# rekick2015-002.net
KiCad netlist of a schematic drawn in EAGLE
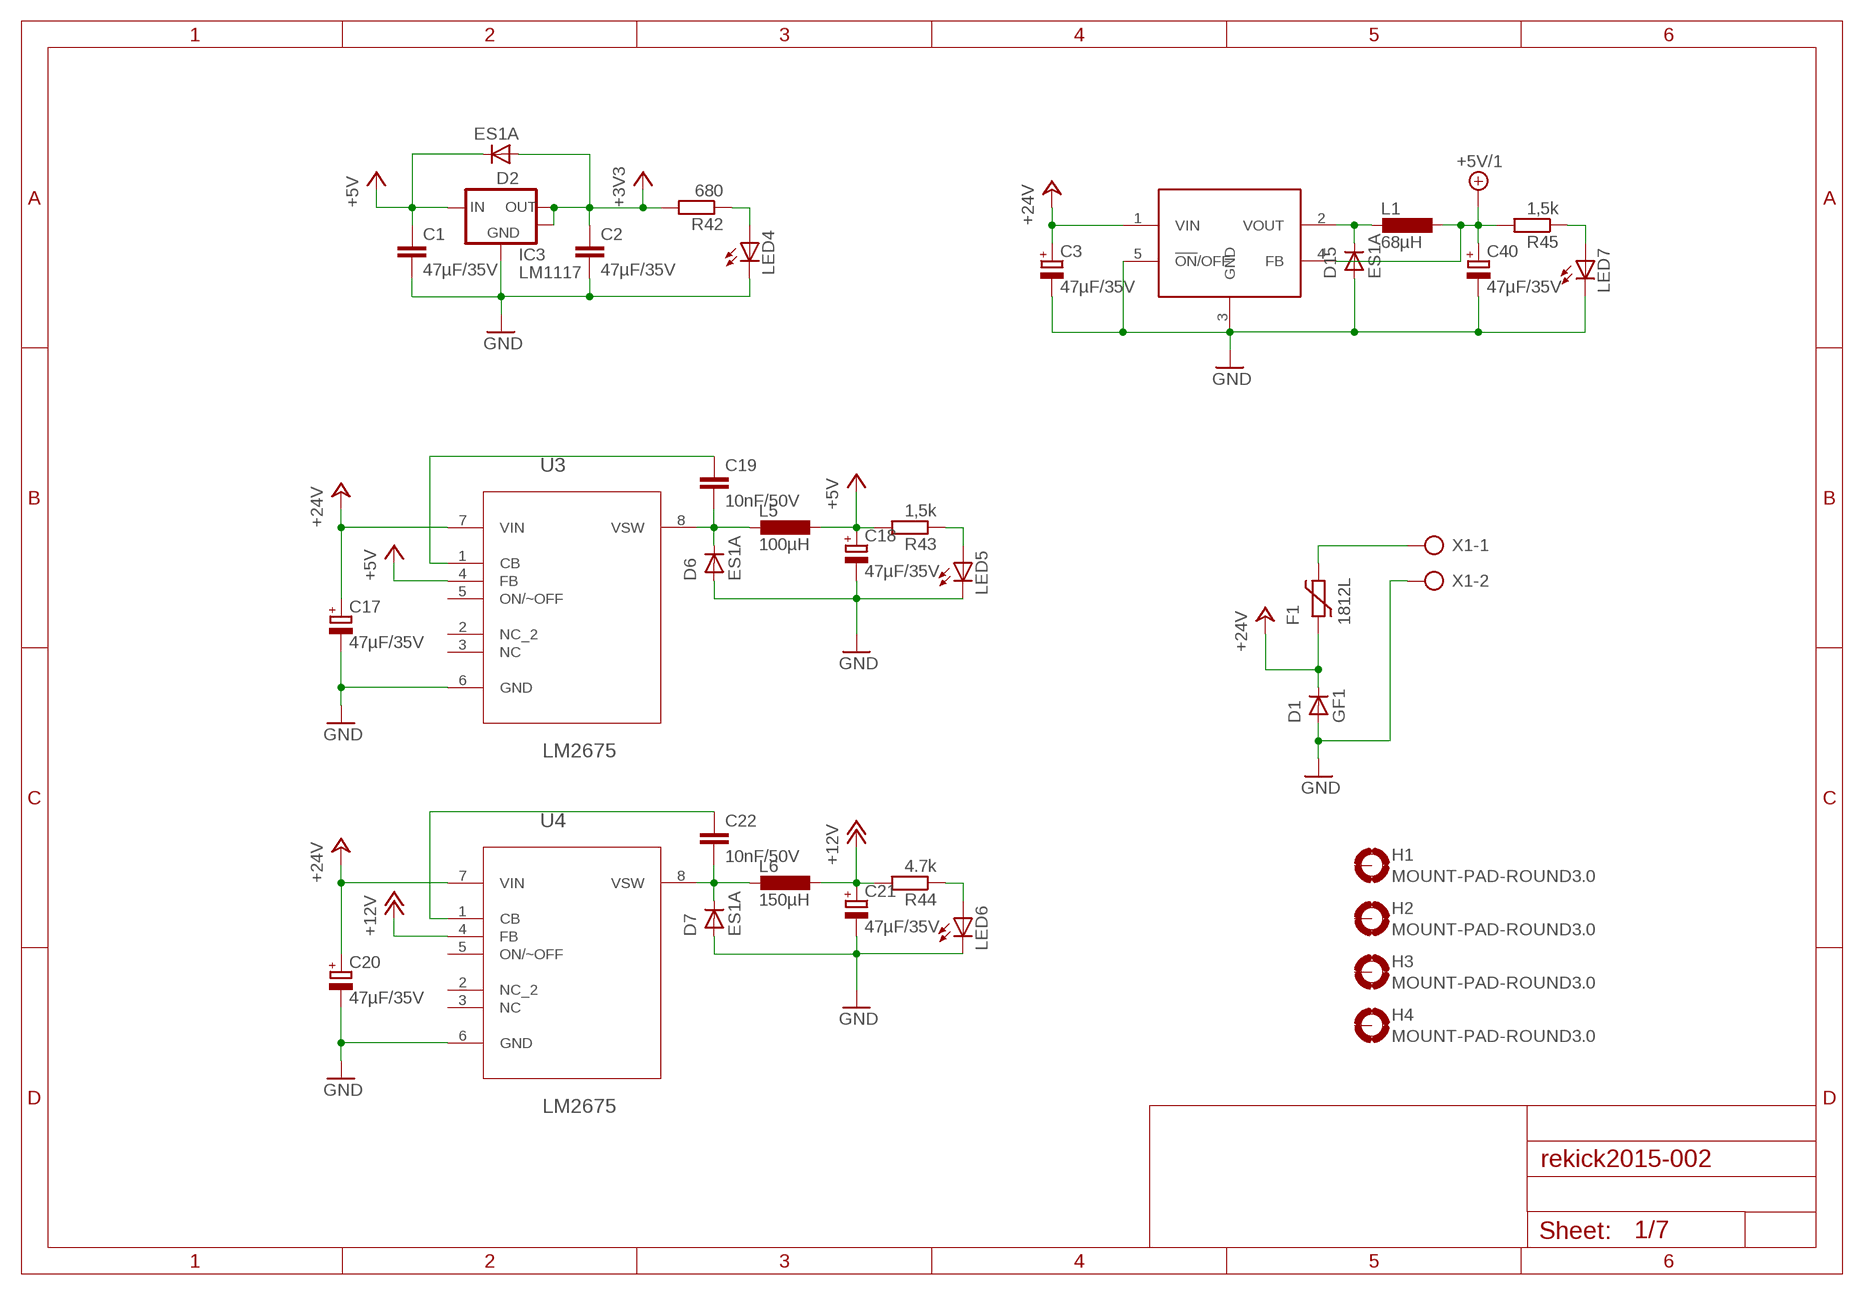
[diagram p0: schematic, sheet 1]
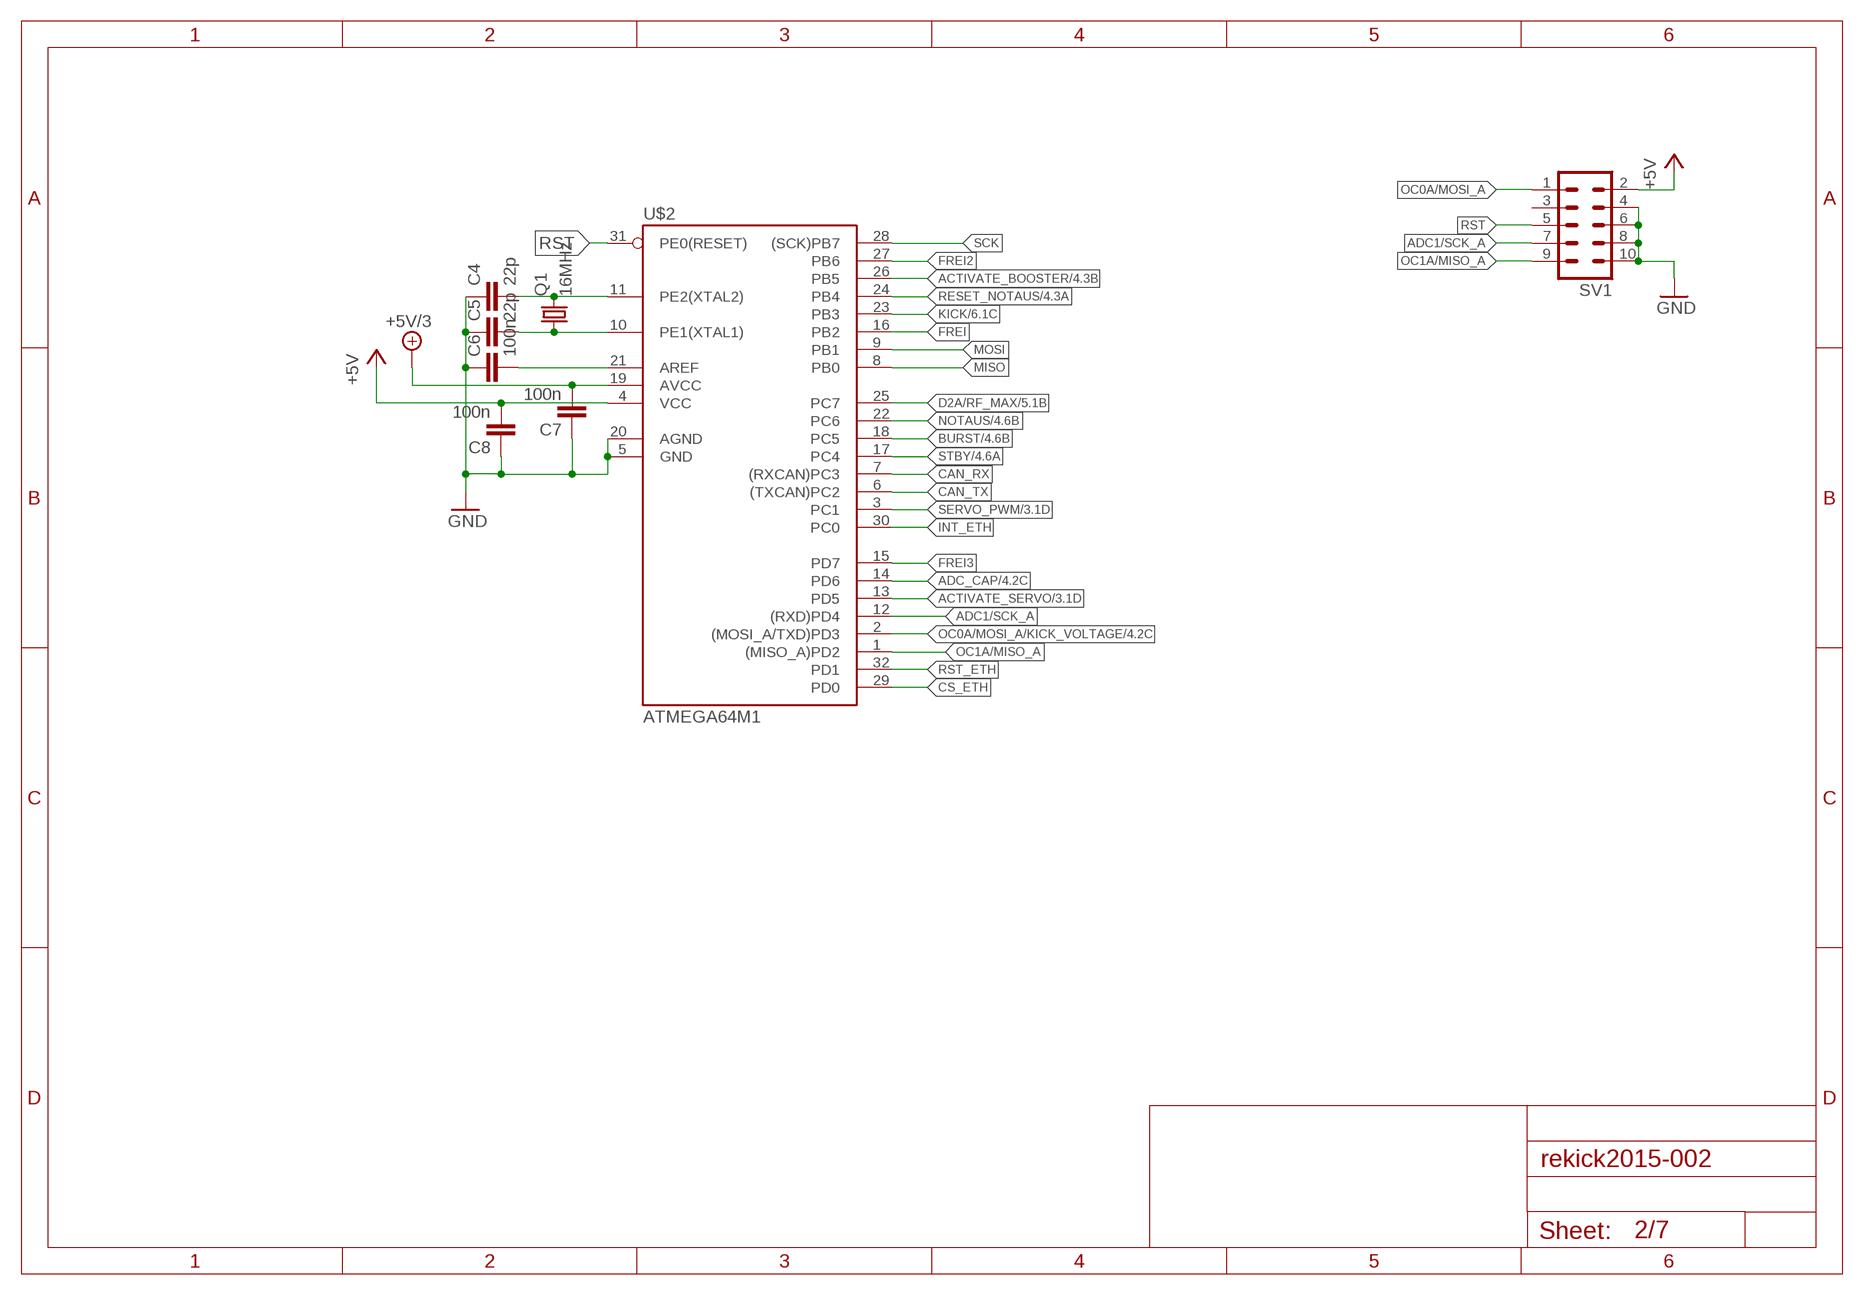
[diagram p1: schematic, sheet 2]
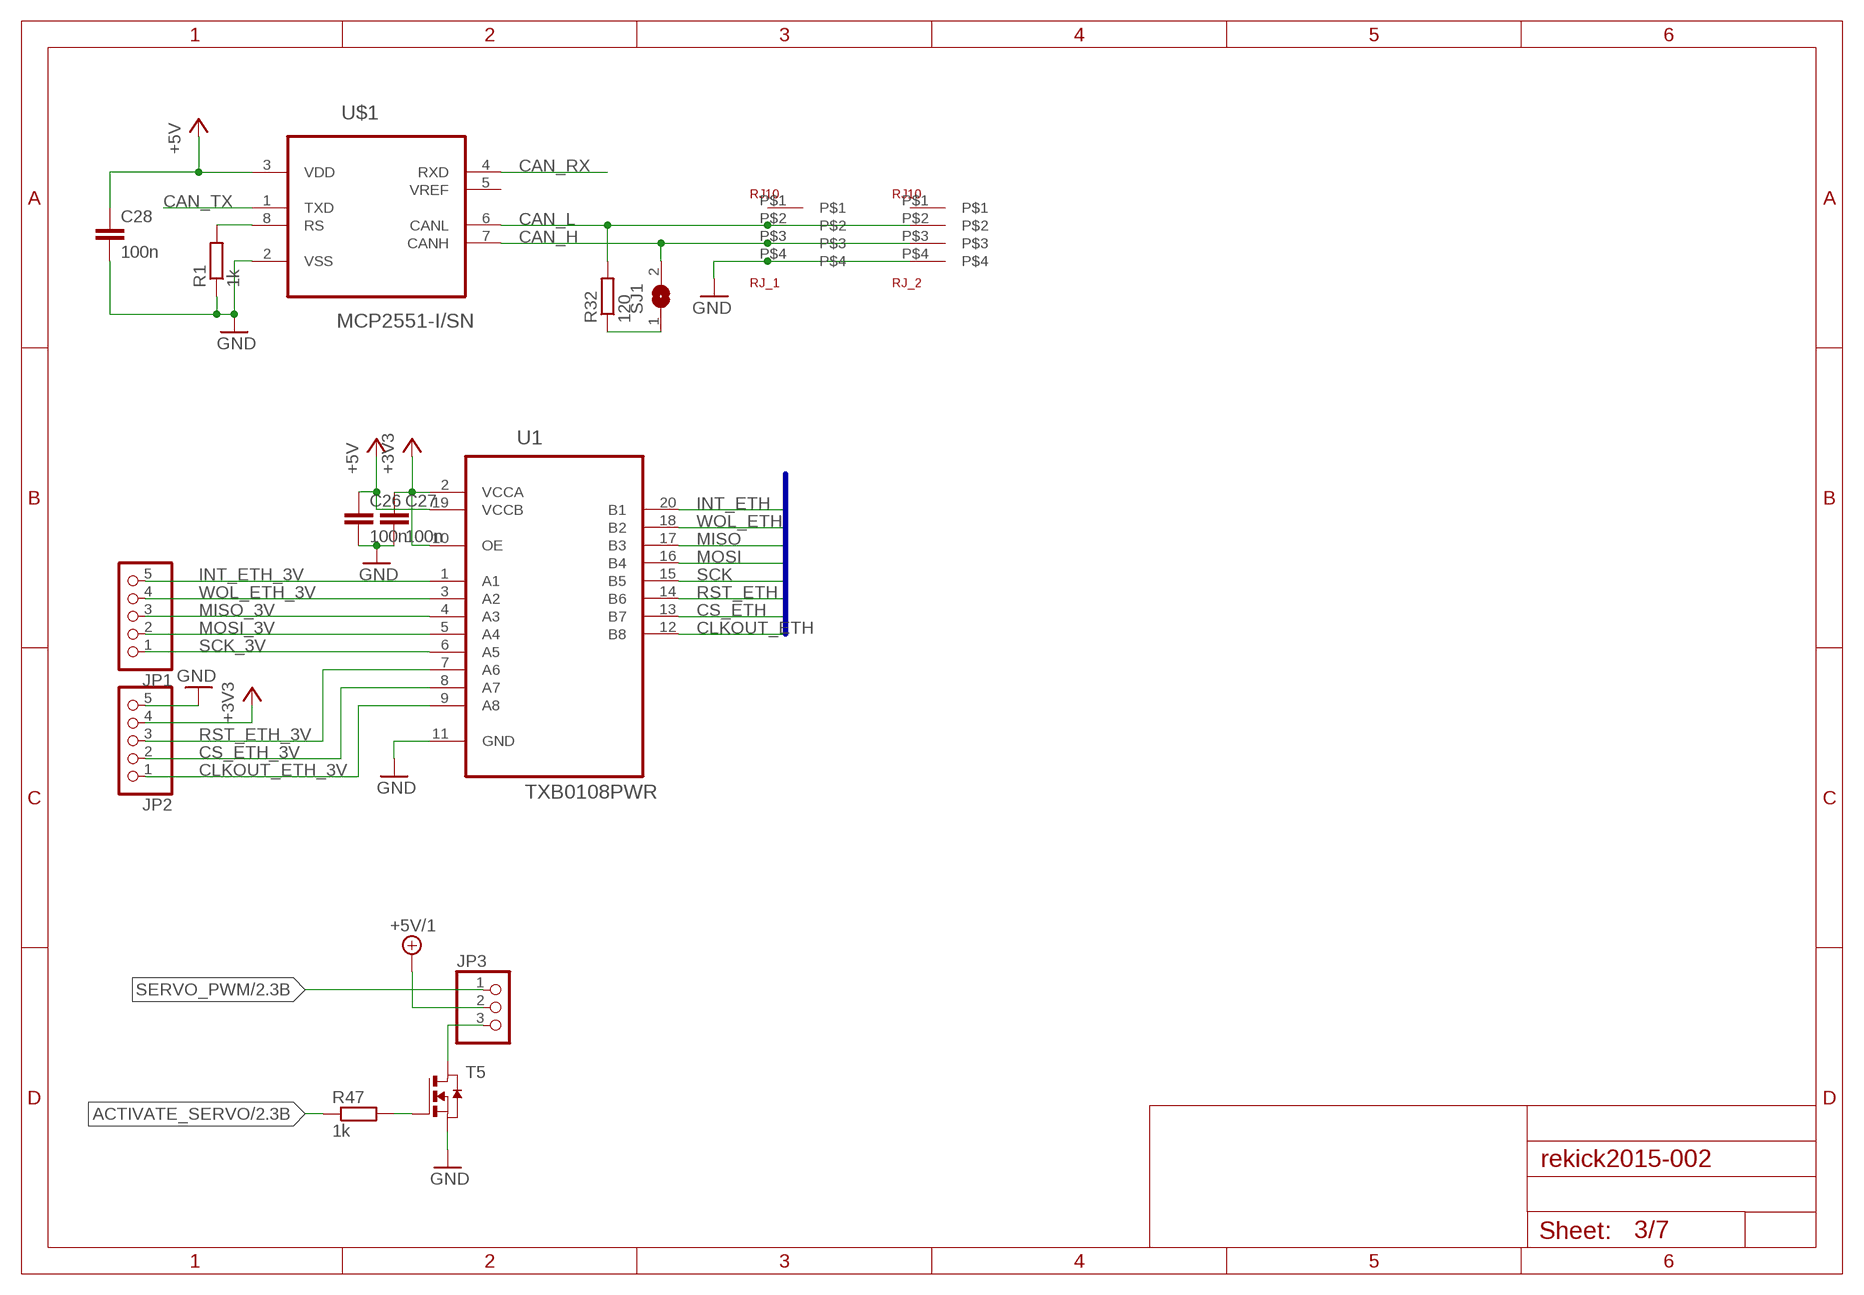
[diagram p2: schematic, sheet 3]
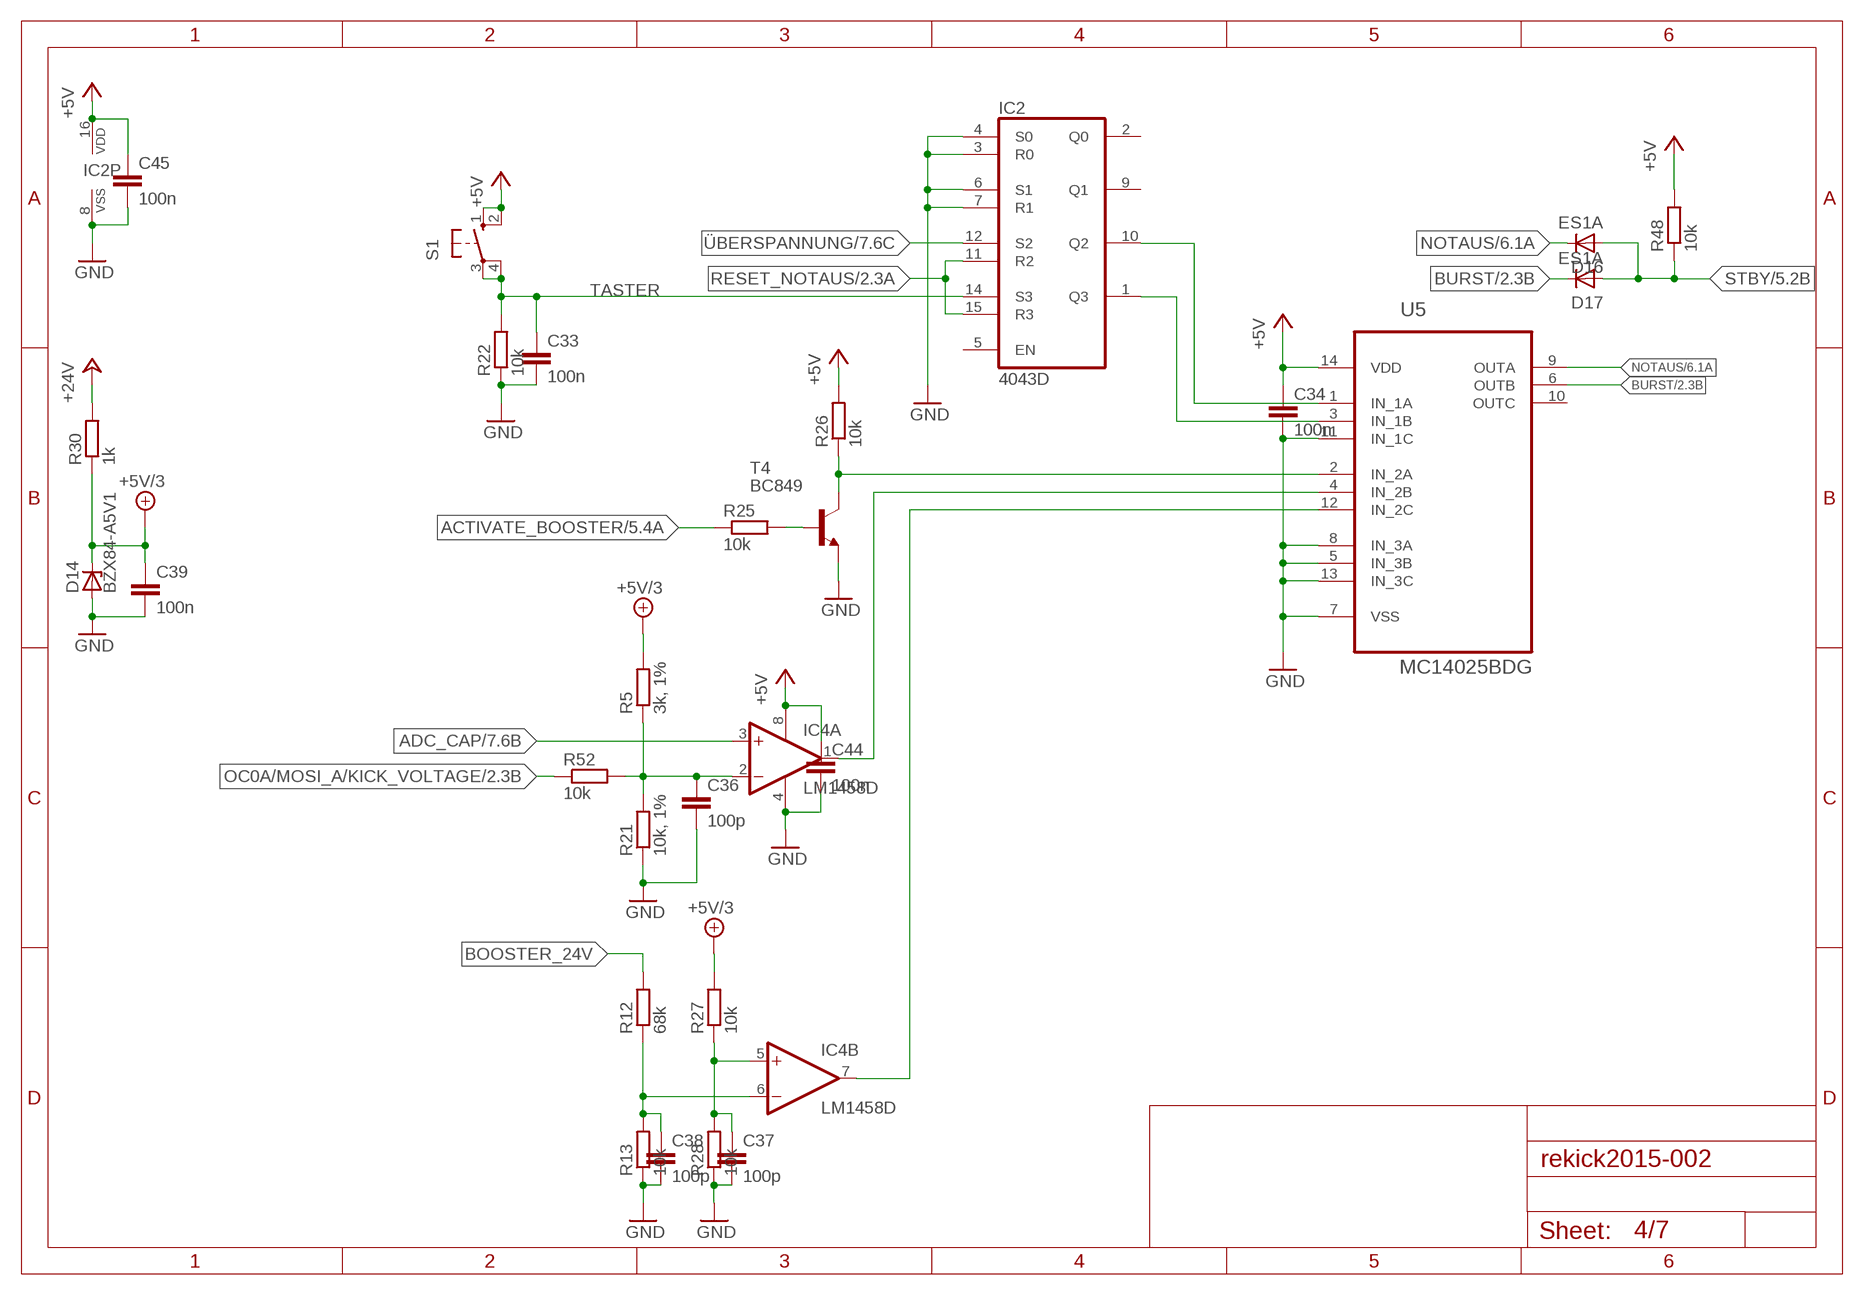
[diagram p3: schematic, sheet 4]
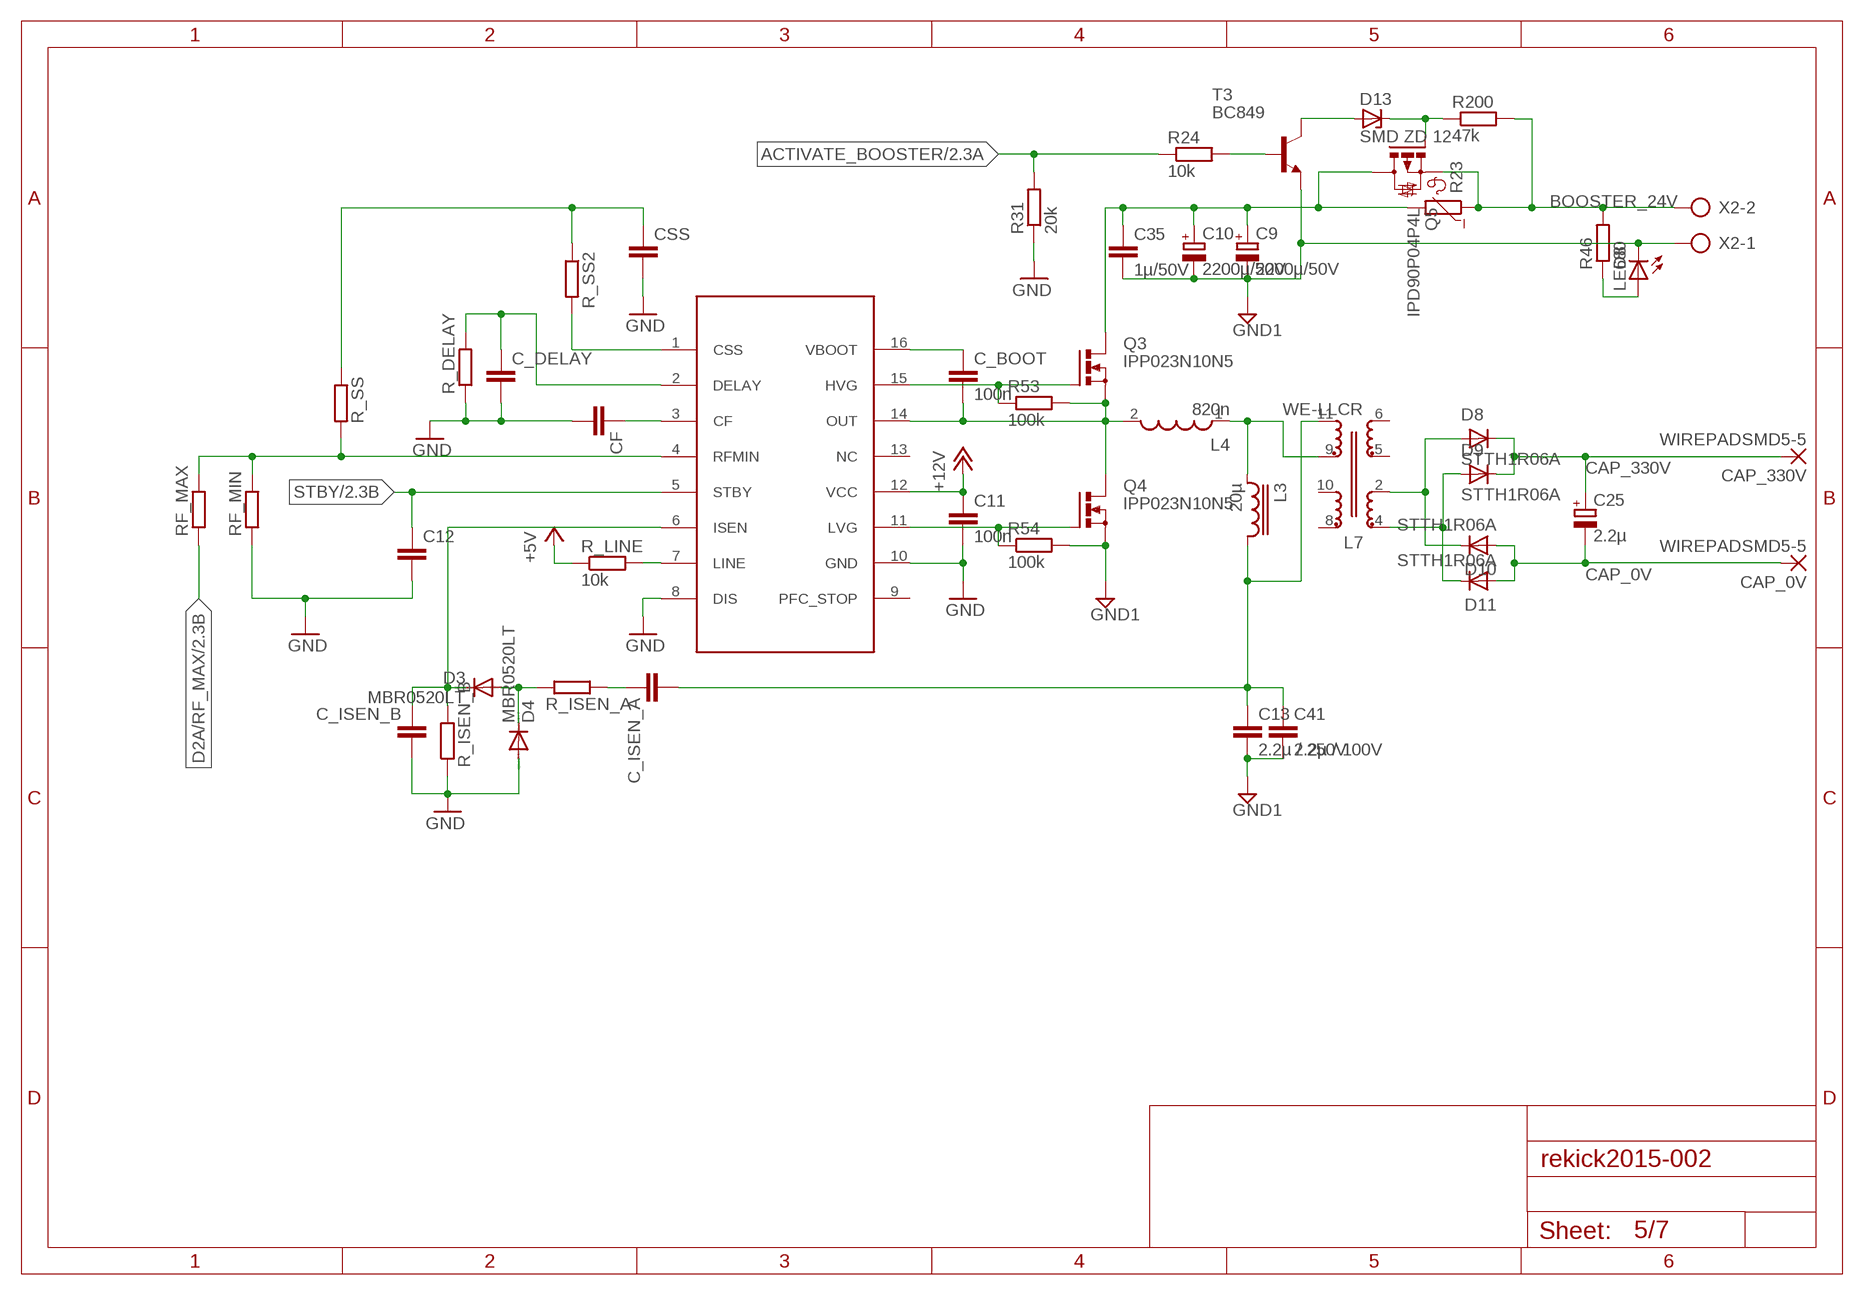
[diagram p4: schematic, sheet 5]
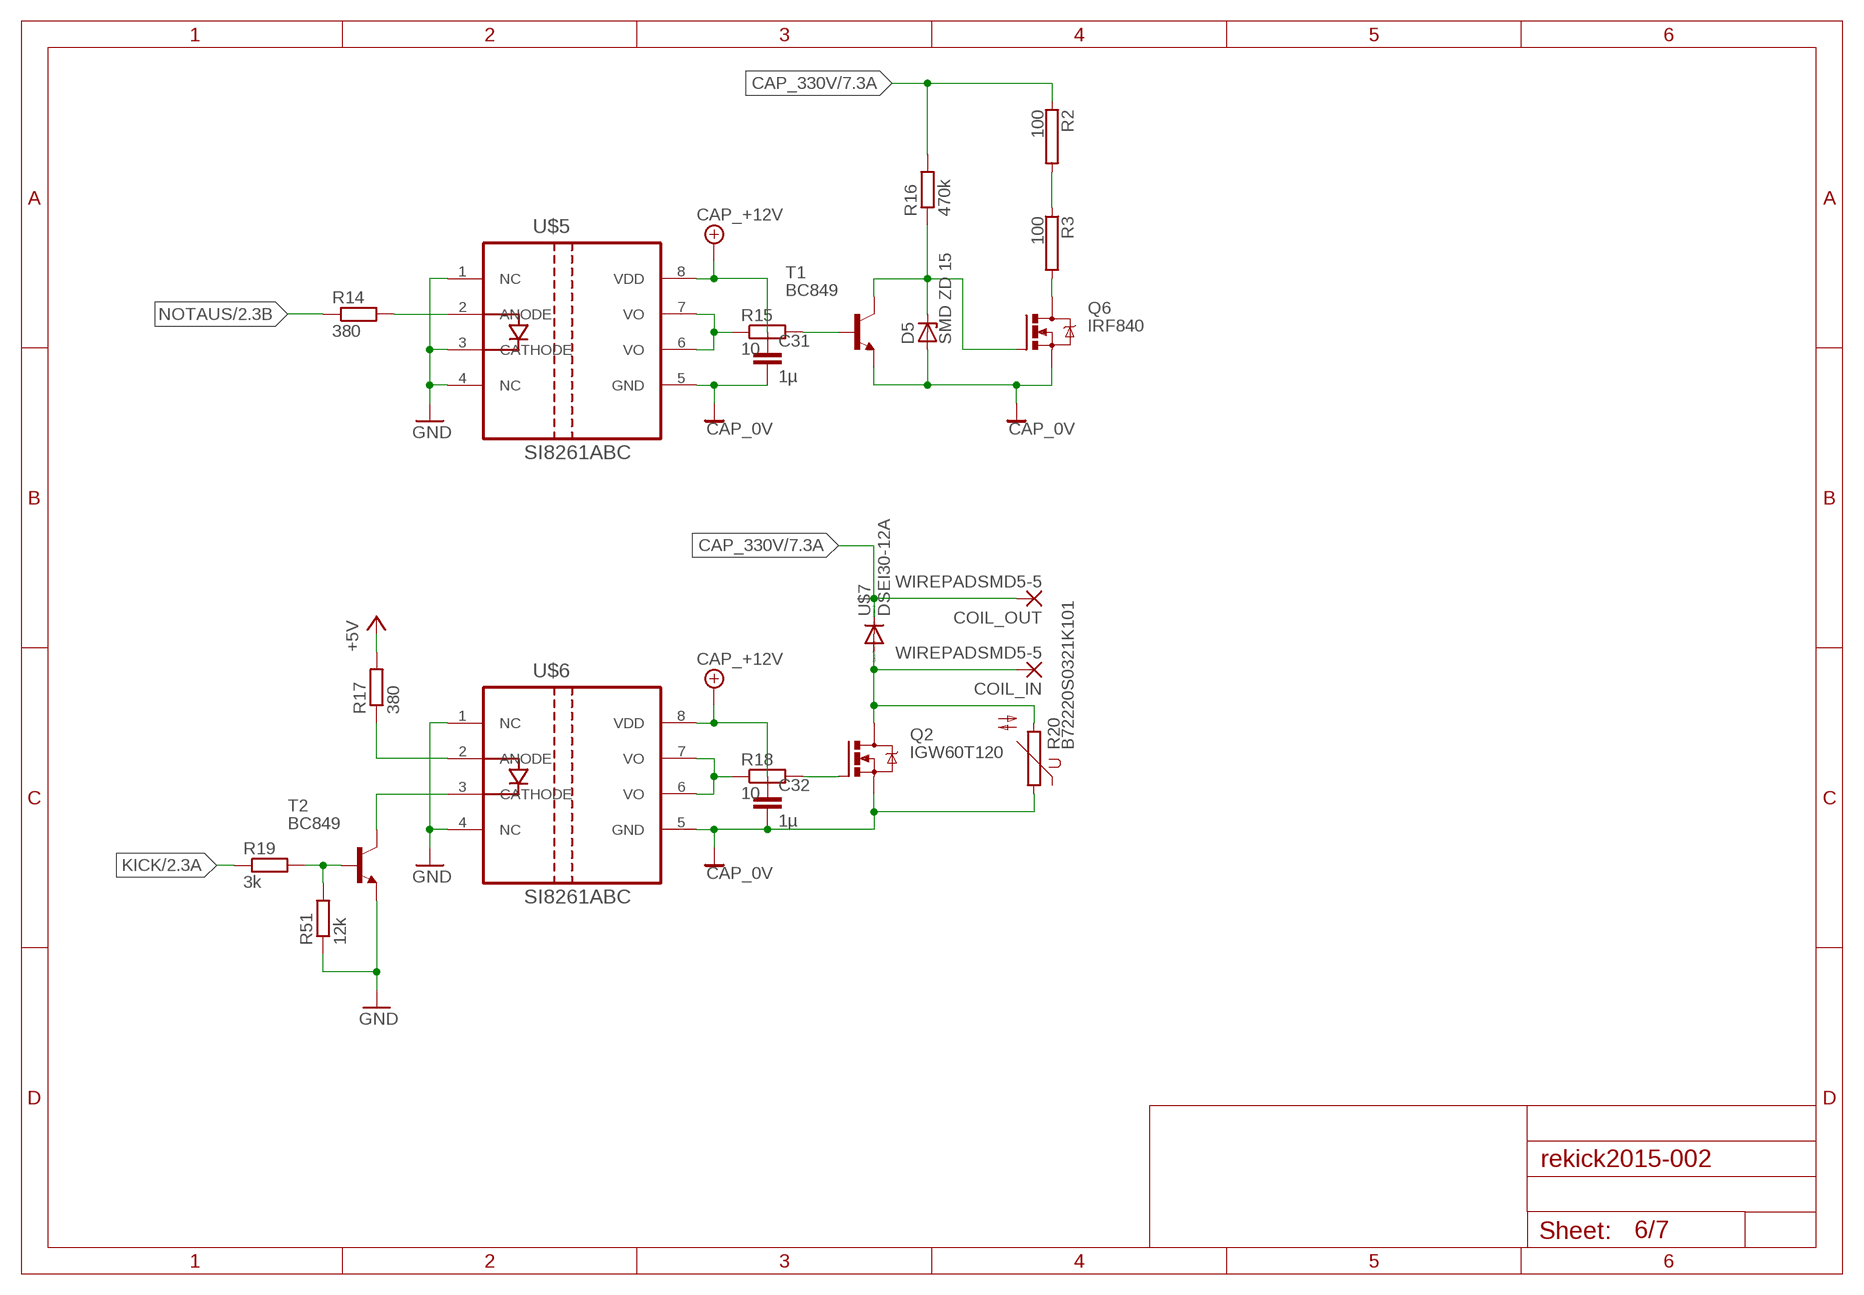
[diagram p5: schematic, sheet 6]
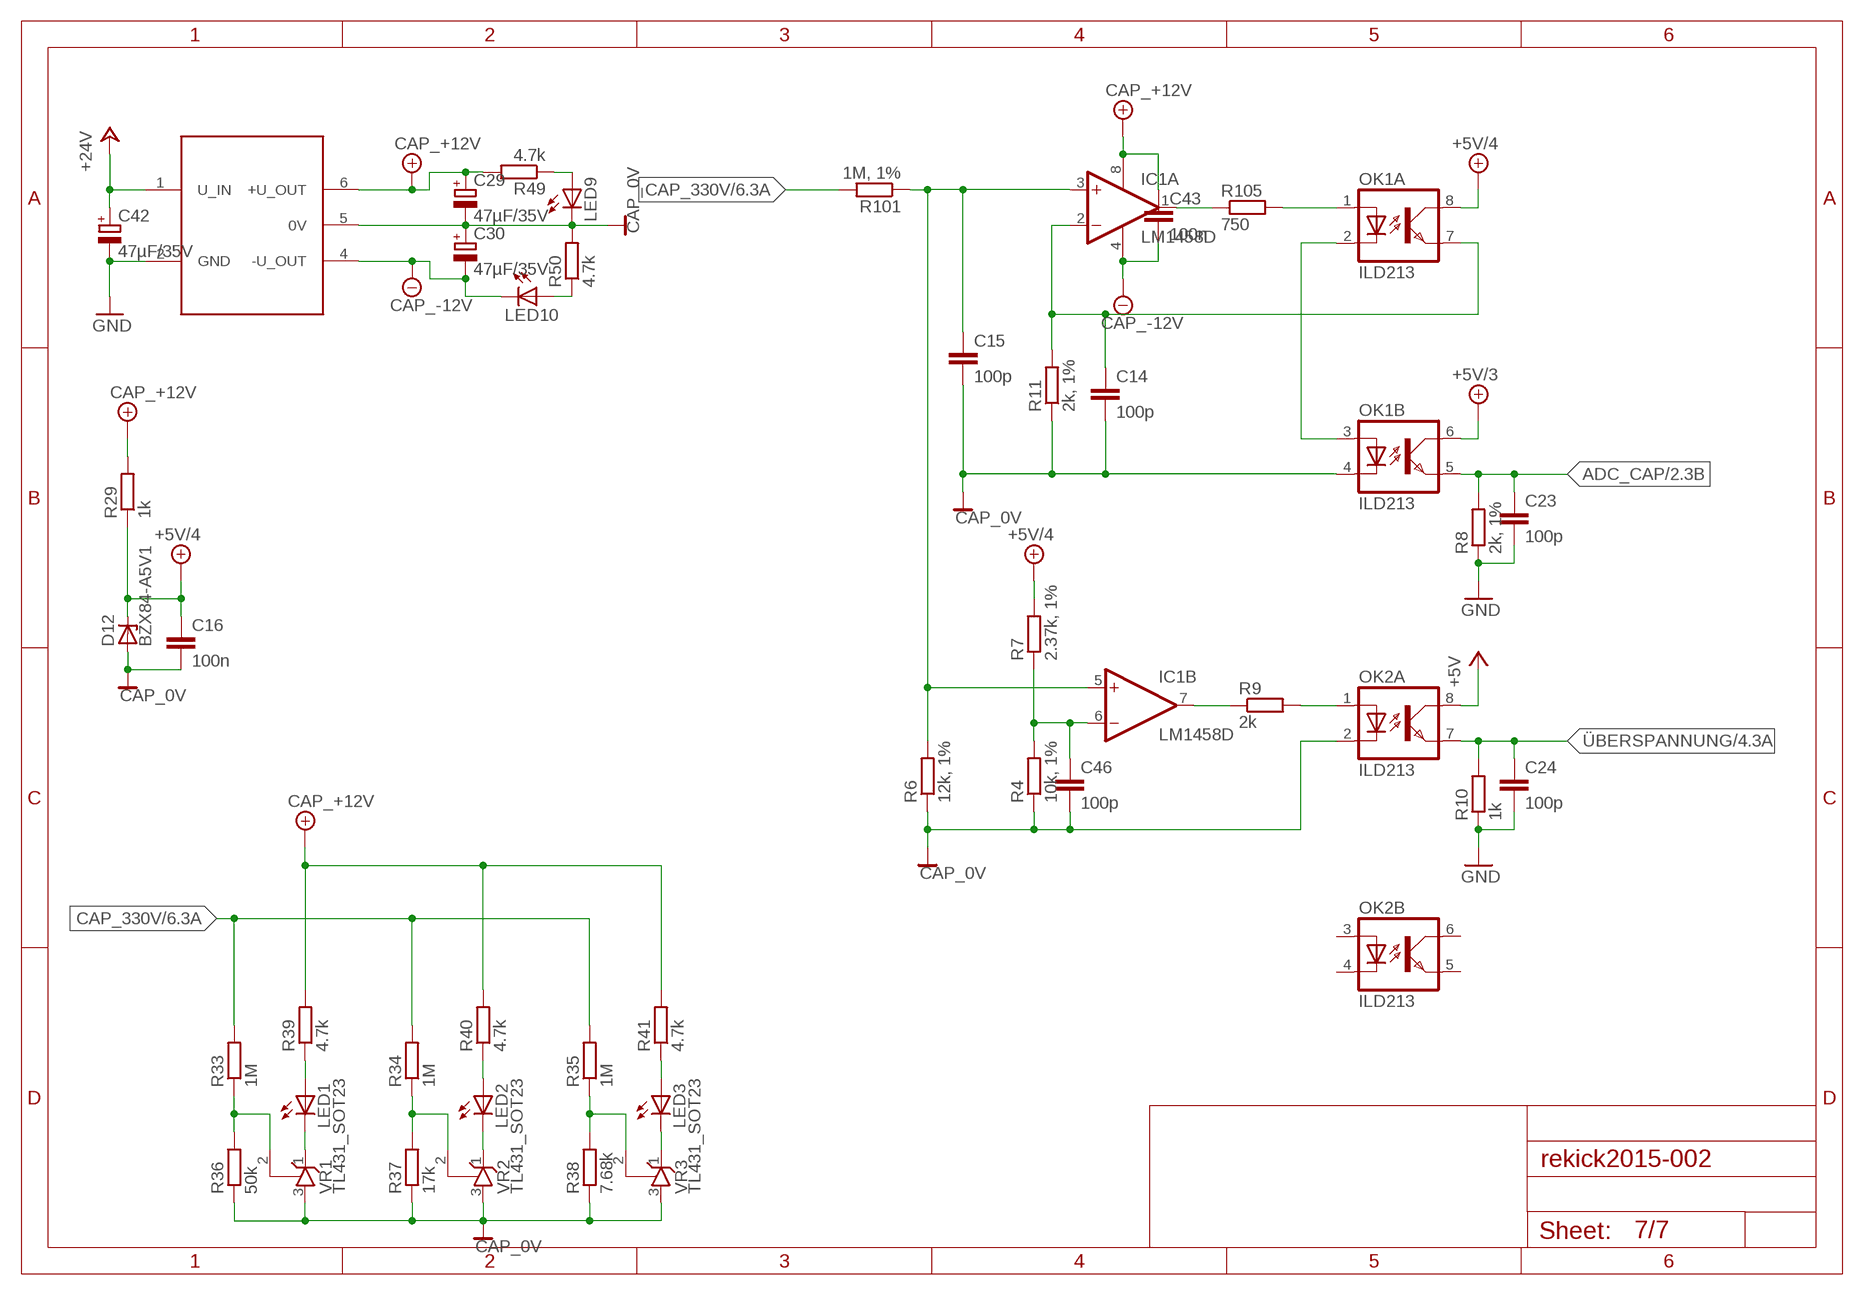
[diagram p6: schematic, sheet 7]

(export (version "E")
  (design (tool "Eeschema 10.0.6"))
  (components
    (comp (ref "C9")
      (value "2200µ/50V")
      (footprint "eagle-import:E5-13")
      (libsource (lib "eagle-import") (part "CPOL-EUE5-13"))
    )
    (comp (ref "C10")
      (value "2200µ/50V")
      (footprint "eagle-import:E5-13")
      (libsource (lib "eagle-import") (part "CPOL-EUE5-13"))
    )
    (comp (ref "C11")
      (value "100n")
      (footprint "eagle-import:C0603")
      (libsource (lib "eagle-import") (part "C-EUC0603"))
    )
    (comp (ref "C12")
      (value "C-EUC0603")
      (footprint "eagle-import:C0603")
      (libsource (lib "eagle-import") (part "C-EUC0603"))
    )
    (comp (ref "C13")
      (value "2.2µ / 250V")
      (footprint "eagle-import:C2220K")
      (libsource (lib "eagle-import") (part "C-EUC2220K"))
    )
    (comp (ref "C25")
      (value "2.2µ")
      (footprint "eagle-import:E5-10,5")
      (libsource (lib "eagle-import") (part "CPOL-EUE5-10.5"))
    )
    (comp (ref "C35")
      (value "1µ/50V")
      (footprint "eagle-import:C0603")
      (libsource (lib "eagle-import") (part "C-EUC0603"))
    )
    (comp (ref "C41")
      (value "2.2µ / 100V")
      (footprint "eagle-import:C1210K")
      (libsource (lib "eagle-import") (part "C-EUC1210K"))
    )
    (comp (ref "CAP_0V")
      (value "WIREPADSMD5-5")
      (footprint "eagle-import:5-5")
      (libsource (lib "eagle-import") (part "WIREPADSMD5-5"))
    )
    (comp (ref "CAP_330V")
      (value "WIREPADSMD5-5")
      (footprint "eagle-import:5-5")
      (libsource (lib "eagle-import") (part "WIREPADSMD5-5"))
    )
    (comp (ref "CF")
      (value "C-EUC0603")
      (footprint "eagle-import:C0603")
      (libsource (lib "eagle-import") (part "C-EUC0603"))
    )
    (comp (ref "CSS")
      (value "C-EUC0603")
      (footprint "eagle-import:C0603")
      (libsource (lib "eagle-import") (part "C-EUC0603"))
    )
    (comp (ref "C_BOOT")
      (value "100n")
      (footprint "eagle-import:C0603")
      (libsource (lib "eagle-import") (part "C-EUC0603"))
    )
    (comp (ref "C_DELAY")
      (value "C-EUC0603")
      (footprint "eagle-import:C0603")
      (libsource (lib "eagle-import") (part "C-EUC0603"))
    )
    (comp (ref "C_ISEN_A")
      (value "C-EUC0603")
      (footprint "eagle-import:C0603")
      (libsource (lib "eagle-import") (part "C-EUC0603"))
    )
    (comp (ref "C_ISEN_B")
      (value "C-EUC0603")
      (footprint "eagle-import:C0603")
      (libsource (lib "eagle-import") (part "C-EUC0603"))
    )
    (comp (ref "D3")
      (value "MBR0520LT")
      (footprint "eagle-import:SOD123")
      (libsource (lib "eagle-import") (part "MBR0520LT"))
    )
    (comp (ref "D4")
      (value "MBR0520LT")
      (footprint "eagle-import:SOD123")
      (libsource (lib "eagle-import") (part "MBR0520LT"))
    )
    (comp (ref "D8")
      (value "STTH1R06A")
      (footprint "eagle-import:SMA-DO214AC")
      (libsource (lib "eagle-import") (part "GF1"))
    )
    (comp (ref "D9")
      (value "STTH1R06A")
      (footprint "eagle-import:SMA-DO214AC")
      (libsource (lib "eagle-import") (part "GF1"))
    )
    (comp (ref "D10")
      (value "STTH1R06A")
      (footprint "eagle-import:SMA-DO214AC")
      (libsource (lib "eagle-import") (part "GF1"))
    )
    (comp (ref "D11")
      (value "STTH1R06A")
      (footprint "eagle-import:SMA-DO214AC")
      (libsource (lib "eagle-import") (part "GF1"))
    )
    (comp (ref "D13")
      (value "SMD ZD 12")
      (footprint "eagle-import:TO236")
      (libsource (lib "eagle-import") (part "BZX84CSMD"))
    )
    (comp (ref "L3")
      (value "20µ")
      (footprint "eagle-import:SRR1210")
      (libsource (lib "eagle-import") (part "SRR1210"))
    )
    (comp (ref "L4")
      (value "820n")
      (footprint "eagle-import:WE-HCI_1890")
      (libsource (lib "eagle-import") (part "WE-HCI_1890"))
    )
    (comp (ref "L7")
      (value "WE-LLCR")
      (footprint "eagle-import:WE-LLCR_ETD34")
      (libsource (lib "eagle-import") (part "WE-LLCR_ETD34"))
    )
    (comp (ref "LED8")
      (value "LEDCHIP-LED0805")
      (footprint "eagle-import:CHIP-LED0805")
      (libsource (lib "eagle-import") (part "LEDCHIP-LED0805"))
    )
    (comp (ref "Q3")
      (value "IPP023N10N5")
      (footprint "eagle-import:TO220BV")
      (libsource (lib "eagle-import") (part "PMOSFET_NTO220BV"))
    )
    (comp (ref "Q4")
      (value "IPP023N10N5")
      (footprint "eagle-import:TO220BV")
      (libsource (lib "eagle-import") (part "PMOSFET_NTO220BV"))
    )
    (comp (ref "Q5")
      (value "IPD90P04P4L")
      (footprint "eagle-import:D-PAK_TO252AA")
      (libsource (lib "eagle-import") (part "IRF?5305R"))
    )
    (comp (ref "R23")
      (value "NTC644A")
      (footprint "eagle-import:N644A")
      (libsource (lib "eagle-import") (part "NTC644A"))
    )
    (comp (ref "R24")
      (value "10k")
      (footprint "eagle-import:R0805")
      (libsource (lib "eagle-import") (part "R-EU_R0805"))
    )
    (comp (ref "R31")
      (value "20k")
      (footprint "eagle-import:R0805")
      (libsource (lib "eagle-import") (part "R-EU_R0805"))
    )
    (comp (ref "R46")
      (value "680")
      (footprint "eagle-import:R0805")
      (libsource (lib "eagle-import") (part "R-EU_R0805"))
    )
    (comp (ref "R53")
      (value "100k")
      (footprint "eagle-import:R0805")
      (libsource (lib "eagle-import") (part "R-EU_R0805"))
    )
    (comp (ref "R54")
      (value "100k")
      (footprint "eagle-import:R0805")
      (libsource (lib "eagle-import") (part "R-EU_R0805"))
    )
    (comp (ref "R200")
      (value "47k")
      (footprint "eagle-import:R0805")
      (libsource (lib "eagle-import") (part "R-EU_R0805"))
    )
    (comp (ref "RF_MAX")
      (value "R-EU_R0805")
      (footprint "eagle-import:R0805")
      (libsource (lib "eagle-import") (part "R-EU_R0805"))
    )
    (comp (ref "RF_MIN")
      (value "R-EU_R0805")
      (footprint "eagle-import:R0805")
      (libsource (lib "eagle-import") (part "R-EU_R0805"))
    )
    (comp (ref "R_DELAY")
      (value "R-EU_R0805")
      (footprint "eagle-import:R0805")
      (libsource (lib "eagle-import") (part "R-EU_R0805"))
    )
    (comp (ref "R_ISEN_A")
      (value "R-EU_R0805")
      (footprint "eagle-import:R0805")
      (libsource (lib "eagle-import") (part "R-EU_R0805"))
    )
    (comp (ref "R_ISEN_B")
      (value "R-EU_R0805")
      (footprint "eagle-import:R0805")
      (libsource (lib "eagle-import") (part "R-EU_R0805"))
    )
    (comp (ref "R_LINE")
      (value "10k")
      (footprint "eagle-import:R0805")
      (libsource (lib "eagle-import") (part "R-EU_R0805"))
    )
    (comp (ref "R_SS")
      (value "R-EU_R0805")
      (footprint "eagle-import:R0805")
      (libsource (lib "eagle-import") (part "R-EU_R0805"))
    )
    (comp (ref "R_SS2")
      (value "R-EU_R0805")
      (footprint "eagle-import:R0805")
      (libsource (lib "eagle-import") (part "R-EU_R0805"))
    )
    (comp (ref "T3")
      (value "BC849")
      (footprint "eagle-import:SOT23")
      (libsource (lib "eagle-import") (part "BC849"))
    )
    (comp (ref "U$3")
      (value "L6599")
      (footprint "eagle-import:SO16")
      (libsource (lib "eagle-import") (part "L6599"))
    )
    (comp (ref "X2")
      (value "AK500/2-H")
      (footprint "eagle-import:AK500_2-H")
      (libsource (lib "eagle-import") (part "AK500/2-H"))
    )
    (comp (ref "C14")
      (value "100p")
      (footprint "eagle-import:C0603")
      (libsource (lib "eagle-import") (part "C-EUC0603"))
    )
    (comp (ref "C15")
      (value "100p")
      (footprint "eagle-import:C0603")
      (libsource (lib "eagle-import") (part "C-EUC0603"))
    )
    (comp (ref "C16")
      (value "100n")
      (footprint "eagle-import:C0603")
      (libsource (lib "eagle-import") (part "C-EUC0603"))
    )
    (comp (ref "C23")
      (value "100p")
      (footprint "eagle-import:C0603")
      (libsource (lib "eagle-import") (part "C-EUC0603"))
    )
    (comp (ref "C24")
      (value "100p")
      (footprint "eagle-import:C0603")
      (libsource (lib "eagle-import") (part "C-EUC0603"))
    )
    (comp (ref "C29")
      (value "47µF/35V")
      (footprint "eagle-import:PANASONIC_D")
      (libsource (lib "eagle-import") (part "CPOL-EUD"))
    )
    (comp (ref "C30")
      (value "47µF/35V")
      (footprint "eagle-import:PANASONIC_D")
      (libsource (lib "eagle-import") (part "CPOL-EUD"))
    )
    (comp (ref "C42")
      (value "47µF/35V")
      (footprint "eagle-import:PANASONIC_D")
      (libsource (lib "eagle-import") (part "CPOL-EUD"))
    )
    (comp (ref "C43")
      (value "100n")
      (footprint "eagle-import:C0603")
      (libsource (lib "eagle-import") (part "C-EUC0603"))
    )
    (comp (ref "C46")
      (value "100p")
      (footprint "eagle-import:C0603")
      (libsource (lib "eagle-import") (part "C-EUC0603"))
    )
    (comp (ref "D12")
      (value "BZX84-A5V1")
      (footprint "eagle-import:TO236")
      (libsource (lib "eagle-import") (part "BZX84CSMD"))
    )
    (comp (ref "IC1")
      (value "LM1458D")
      (footprint "eagle-import:SO08")
      (libsource (lib "eagle-import") (part "1458DLM"))
    )
    (comp (ref "LED1")
      (value "LEDCHIP-LED0805")
      (footprint "eagle-import:CHIP-LED0805")
      (libsource (lib "eagle-import") (part "LEDCHIP-LED0805"))
    )
    (comp (ref "LED2")
      (value "LEDCHIP-LED0805")
      (footprint "eagle-import:CHIP-LED0805")
      (libsource (lib "eagle-import") (part "LEDCHIP-LED0805"))
    )
    (comp (ref "LED3")
      (value "LEDCHIP-LED0805")
      (footprint "eagle-import:CHIP-LED0805")
      (libsource (lib "eagle-import") (part "LEDCHIP-LED0805"))
    )
    (comp (ref "LED9")
      (value "LEDCHIP-LED0805")
      (footprint "eagle-import:CHIP-LED0805")
      (libsource (lib "eagle-import") (part "LEDCHIP-LED0805"))
    )
    (comp (ref "LED10")
      (value "LEDCHIP-LED0805")
      (footprint "eagle-import:CHIP-LED0805")
      (libsource (lib "eagle-import") (part "LEDCHIP-LED0805"))
    )
    (comp (ref "OK1")
      (value "ILD213")
      (footprint "eagle-import:SOIC08")
      (libsource (lib "eagle-import") (part "ILD213"))
    )
    (comp (ref "OK2")
      (value "ILD213")
      (footprint "eagle-import:SOIC08")
      (libsource (lib "eagle-import") (part "ILD213"))
    )
    (comp (ref "R4")
      (value "10k, 1%")
      (footprint "eagle-import:R0805")
      (libsource (lib "eagle-import") (part "R-EU_R0805"))
    )
    (comp (ref "R6")
      (value "12k, 1%")
      (footprint "eagle-import:R0805")
      (libsource (lib "eagle-import") (part "R-EU_R0805"))
    )
    (comp (ref "R7")
      (value "2.37k, 1%")
      (footprint "eagle-import:R0805")
      (libsource (lib "eagle-import") (part "R-EU_R0805"))
    )
    (comp (ref "R8")
      (value "2k, 1%")
      (footprint "eagle-import:R0805")
      (libsource (lib "eagle-import") (part "R-EU_R0805"))
    )
    (comp (ref "R9")
      (value "2k")
      (footprint "eagle-import:R0805")
      (libsource (lib "eagle-import") (part "R-EU_R0805"))
    )
    (comp (ref "R10")
      (value "1k")
      (footprint "eagle-import:R0805")
      (libsource (lib "eagle-import") (part "R-EU_R0805"))
    )
    (comp (ref "R11")
      (value "2k, 1%")
      (footprint "eagle-import:R0805")
      (libsource (lib "eagle-import") (part "R-EU_R0805"))
    )
    (comp (ref "R29")
      (value "1k")
      (footprint "eagle-import:R0805")
      (libsource (lib "eagle-import") (part "R-EU_R0805"))
    )
    (comp (ref "R33")
      (value "1M")
      (footprint "eagle-import:R2512")
      (libsource (lib "eagle-import") (part "R-EU_R2512"))
    )
    (comp (ref "R34")
      (value "1M")
      (footprint "eagle-import:R2512")
      (libsource (lib "eagle-import") (part "R-EU_R2512"))
    )
    (comp (ref "R35")
      (value "1M")
      (footprint "eagle-import:R2512")
      (libsource (lib "eagle-import") (part "R-EU_R2512"))
    )
    (comp (ref "R36")
      (value "50k")
      (footprint "eagle-import:R0805")
      (libsource (lib "eagle-import") (part "R-EU_R0805"))
    )
    (comp (ref "R37")
      (value "17k")
      (footprint "eagle-import:R0805")
      (libsource (lib "eagle-import") (part "R-EU_R0805"))
    )
    (comp (ref "R38")
      (value "7.68k")
      (footprint "eagle-import:R0805")
      (libsource (lib "eagle-import") (part "R-EU_R0805"))
    )
    (comp (ref "R39")
      (value "4.7k")
      (footprint "eagle-import:R0805")
      (libsource (lib "eagle-import") (part "R-EU_R0805"))
    )
    (comp (ref "R40")
      (value "4.7k")
      (footprint "eagle-import:R0805")
      (libsource (lib "eagle-import") (part "R-EU_R0805"))
    )
    (comp (ref "R41")
      (value "4.7k")
      (footprint "eagle-import:R0805")
      (libsource (lib "eagle-import") (part "R-EU_R0805"))
    )
    (comp (ref "R49")
      (value "4.7k")
      (footprint "eagle-import:R0805")
      (libsource (lib "eagle-import") (part "R-EU_R0805"))
    )
    (comp (ref "R50")
      (value "4.7k")
      (footprint "eagle-import:R0805")
      (libsource (lib "eagle-import") (part "R-EU_R0805"))
    )
    (comp (ref "R101")
      (value "1M, 1%")
      (footprint "eagle-import:R2512")
      (libsource (lib "eagle-import") (part "R-EU_R2512"))
    )
    (comp (ref "R105")
      (value "750")
      (footprint "eagle-import:R0805")
      (libsource (lib "eagle-import") (part "R-EU_R0805"))
    )
    (comp (ref "U$4")
      (value "TMH-D")
      (footprint "eagle-import:TMH-D")
      (libsource (lib "eagle-import") (part "TMH-D"))
    )
    (comp (ref "VR1")
      (value "TL431_SOT23")
      (footprint "eagle-import:SOT23")
      (libsource (lib "eagle-import") (part "TL431_SOT23"))
    )
    (comp (ref "VR2")
      (value "TL431_SOT23")
      (footprint "eagle-import:SOT23")
      (libsource (lib "eagle-import") (part "TL431_SOT23"))
    )
    (comp (ref "VR3")
      (value "TL431_SOT23")
      (footprint "eagle-import:SOT23")
      (libsource (lib "eagle-import") (part "TL431_SOT23"))
    )
    (comp (ref "C4")
      (value "22p")
      (footprint "eagle-import:C0603")
      (libsource (lib "eagle-import") (part "C-EUC0603"))
    )
    (comp (ref "C5")
      (value "22p")
      (footprint "eagle-import:C0603")
      (libsource (lib "eagle-import") (part "C-EUC0603"))
    )
    (comp (ref "C6")
      (value "100n")
      (footprint "eagle-import:C0603")
      (libsource (lib "eagle-import") (part "C-EUC0603"))
    )
    (comp (ref "C7")
      (value "100n")
      (footprint "eagle-import:C0603")
      (libsource (lib "eagle-import") (part "C-EUC0603"))
    )
    (comp (ref "C8")
      (value "100n")
      (footprint "eagle-import:C0603")
      (libsource (lib "eagle-import") (part "C-EUC0603"))
    )
    (comp (ref "Q1")
      (value "16MHz")
      (footprint "eagle-import:HC49UP")
      (libsource (lib "eagle-import") (part "CRYSTALHC49UP"))
    )
    (comp (ref "SV1")
      (value "ML10")
      (footprint "eagle-import:ML10")
      (libsource (lib "eagle-import") (part "ML10"))
    )
    (comp (ref "U$2")
      (value "ATMEGA64M1")
      (footprint "eagle-import:TQFP32-08")
      (libsource (lib "eagle-import") (part "ATMEGA64M1"))
    )
    (comp (ref "C33")
      (value "100n")
      (footprint "eagle-import:C0603")
      (libsource (lib "eagle-import") (part "C-EUC0603"))
    )
    (comp (ref "C34")
      (value "100n")
      (footprint "eagle-import:C0603")
      (libsource (lib "eagle-import") (part "C-EUC0603"))
    )
    (comp (ref "C36")
      (value "100p")
      (footprint "eagle-import:C0603")
      (libsource (lib "eagle-import") (part "C-EUC0603"))
    )
    (comp (ref "C37")
      (value "100p")
      (footprint "eagle-import:C0603")
      (libsource (lib "eagle-import") (part "C-EUC0603"))
    )
    (comp (ref "C38")
      (value "100p")
      (footprint "eagle-import:C0603")
      (libsource (lib "eagle-import") (part "C-EUC0603"))
    )
    (comp (ref "C39")
      (value "100n")
      (footprint "eagle-import:C0603")
      (libsource (lib "eagle-import") (part "C-EUC0603"))
    )
    (comp (ref "C44")
      (value "100n")
      (footprint "eagle-import:C0603")
      (libsource (lib "eagle-import") (part "C-EUC0603"))
    )
    (comp (ref "C45")
      (value "100n")
      (footprint "eagle-import:C0603")
      (libsource (lib "eagle-import") (part "C-EUC0603"))
    )
    (comp (ref "D14")
      (value "BZX84-A5V1")
      (footprint "eagle-import:TO236")
      (libsource (lib "eagle-import") (part "BZX84CSMD"))
    )
    (comp (ref "D16")
      (value "ES1A")
      (footprint "eagle-import:SMA-DO214AC")
      (libsource (lib "eagle-import") (part "GF1"))
    )
    (comp (ref "D17")
      (value "ES1A")
      (footprint "eagle-import:SMA-DO214AC")
      (libsource (lib "eagle-import") (part "GF1"))
    )
    (comp (ref "IC2")
      (value "4043D")
      (footprint "eagle-import:SO16")
      (libsource (lib "eagle-import") (part "4043D"))
    )
    (comp (ref "IC4")
      (value "LM1458D")
      (footprint "eagle-import:SO08")
      (libsource (lib "eagle-import") (part "1458DLM"))
    )
    (comp (ref "R5")
      (value "3k, 1%")
      (footprint "eagle-import:R0805")
      (libsource (lib "eagle-import") (part "R-EU_R0805"))
    )
    (comp (ref "R12")
      (value "68k")
      (footprint "eagle-import:R0805")
      (libsource (lib "eagle-import") (part "R-EU_R0805"))
    )
    (comp (ref "R13")
      (value "10k")
      (footprint "eagle-import:R0805")
      (libsource (lib "eagle-import") (part "R-EU_R0805"))
    )
    (comp (ref "R21")
      (value "10k, 1%")
      (footprint "eagle-import:R0805")
      (libsource (lib "eagle-import") (part "R-EU_R0805"))
    )
    (comp (ref "R22")
      (value "10k")
      (footprint "eagle-import:R0805")
      (libsource (lib "eagle-import") (part "R-EU_R0805"))
    )
    (comp (ref "R25")
      (value "10k")
      (footprint "eagle-import:R0805")
      (libsource (lib "eagle-import") (part "R-EU_R0805"))
    )
    (comp (ref "R26")
      (value "10k")
      (footprint "eagle-import:R0805")
      (libsource (lib "eagle-import") (part "R-EU_R0805"))
    )
    (comp (ref "R27")
      (value "10k")
      (footprint "eagle-import:R0805")
      (libsource (lib "eagle-import") (part "R-EU_R0805"))
    )
    (comp (ref "R28")
      (value "10k")
      (footprint "eagle-import:R0805")
      (libsource (lib "eagle-import") (part "R-EU_R0805"))
    )
    (comp (ref "R30")
      (value "1k")
      (footprint "eagle-import:R0805")
      (libsource (lib "eagle-import") (part "R-EU_R0805"))
    )
    (comp (ref "R48")
      (value "10k")
      (footprint "eagle-import:R0805")
      (libsource (lib "eagle-import") (part "R-EU_R0805"))
    )
    (comp (ref "R52")
      (value "10k")
      (footprint "eagle-import:R0805")
      (libsource (lib "eagle-import") (part "R-EU_R0805"))
    )
    (comp (ref "S1")
      (value "10-XX")
      (footprint "eagle-import:B3F-10XX")
      (libsource (lib "eagle-import") (part "10-XX"))
    )
    (comp (ref "T4")
      (value "BC849")
      (footprint "eagle-import:SOT23")
      (libsource (lib "eagle-import") (part "BC849"))
    )
    (comp (ref "U5")
      (value "MC14025BDG")
      (footprint "eagle-import:SOIC127P600X175-14N")
      (libsource (lib "eagle-import") (part "MC14025BDG"))
    )
    (comp (ref "C1")
      (value "47µF/35V")
      (footprint "eagle-import:C0603")
      (libsource (lib "eagle-import") (part "C-EUC0603"))
    )
    (comp (ref "C2")
      (value "47µF/35V")
      (footprint "eagle-import:C0603")
      (libsource (lib "eagle-import") (part "C-EUC0603"))
    )
    (comp (ref "C3")
      (value "47µF/35V")
      (footprint "eagle-import:PANASONIC_D")
      (libsource (lib "eagle-import") (part "CPOL-EUD"))
    )
    (comp (ref "C17")
      (value "47µF/35V")
      (footprint "eagle-import:PANASONIC_D")
      (libsource (lib "eagle-import") (part "CPOL-EUD"))
    )
    (comp (ref "C18")
      (value "47µF/35V")
      (footprint "eagle-import:PANASONIC_D")
      (libsource (lib "eagle-import") (part "CPOL-EUD"))
    )
    (comp (ref "C19")
      (value "10nF/50V")
      (footprint "eagle-import:C0603")
      (libsource (lib "eagle-import") (part "C-EUC0603"))
    )
    (comp (ref "C20")
      (value "47µF/35V")
      (footprint "eagle-import:PANASONIC_D")
      (libsource (lib "eagle-import") (part "CPOL-EUD"))
    )
    (comp (ref "C21")
      (value "47µF/35V")
      (footprint "eagle-import:PANASONIC_D")
      (libsource (lib "eagle-import") (part "CPOL-EUD"))
    )
    (comp (ref "C22")
      (value "10nF/50V")
      (footprint "eagle-import:C0603")
      (libsource (lib "eagle-import") (part "C-EUC0603"))
    )
    (comp (ref "C40")
      (value "47µF/35V")
      (footprint "eagle-import:PANASONIC_D")
      (libsource (lib "eagle-import") (part "CPOL-EUD"))
    )
    (comp (ref "D1")
      (value "GF1")
      (footprint "eagle-import:SMA-DO214AC")
      (libsource (lib "eagle-import") (part "GF1"))
    )
    (comp (ref "D2")
      (value "ES1A")
      (footprint "eagle-import:SMA-DO214AC")
      (libsource (lib "eagle-import") (part "GF1"))
    )
    (comp (ref "D6")
      (value "ES1A")
      (footprint "eagle-import:SMA-DO214AC")
      (libsource (lib "eagle-import") (part "GF1"))
    )
    (comp (ref "D7")
      (value "ES1A")
      (footprint "eagle-import:SMA-DO214AC")
      (libsource (lib "eagle-import") (part "GF1"))
    )
    (comp (ref "D15")
      (value "ES1A")
      (footprint "eagle-import:SMA-DO214AC")
      (libsource (lib "eagle-import") (part "GF1"))
    )
    (comp (ref "F1")
      (value "1812L")
      (footprint "eagle-import:1812L")
      (libsource (lib "eagle-import") (part "1812L"))
    )
    (comp (ref "H1")
      (value "MOUNT-PAD-ROUND3.0")
      (footprint "eagle-import:3,0-PAD")
      (libsource (lib "eagle-import") (part "MOUNT-PAD-ROUND3.0"))
    )
    (comp (ref "H2")
      (value "MOUNT-PAD-ROUND3.0")
      (footprint "eagle-import:3,0-PAD")
      (libsource (lib "eagle-import") (part "MOUNT-PAD-ROUND3.0"))
    )
    (comp (ref "H3")
      (value "MOUNT-PAD-ROUND3.0")
      (footprint "eagle-import:3,0-PAD")
      (libsource (lib "eagle-import") (part "MOUNT-PAD-ROUND3.0"))
    )
    (comp (ref "H4")
      (value "MOUNT-PAD-ROUND3.0")
      (footprint "eagle-import:3,0-PAD")
      (libsource (lib "eagle-import") (part "MOUNT-PAD-ROUND3.0"))
    )
    (comp (ref "IC3")
      (value "LM1117")
      (footprint "eagle-import:SOT223")
      (libsource (lib "eagle-import") (part "LM1117"))
    )
    (comp (ref "L1")
      (value "68µH")
      (footprint "eagle-import:PISM")
      (libsource (lib "eagle-import") (part "L-EUPISM"))
    )
    (comp (ref "L5")
      (value "100µH")
      (footprint "eagle-import:PISM")
      (libsource (lib "eagle-import") (part "L-EUPISM"))
    )
    (comp (ref "L6")
      (value "150µH")
      (footprint "eagle-import:PISM")
      (libsource (lib "eagle-import") (part "L-EUPISM"))
    )
    (comp (ref "LED4")
      (value "LEDCHIP-LED0805")
      (footprint "eagle-import:CHIP-LED0805")
      (libsource (lib "eagle-import") (part "LEDCHIP-LED0805"))
    )
    (comp (ref "LED5")
      (value "LEDCHIP-LED0805")
      (footprint "eagle-import:CHIP-LED0805")
      (libsource (lib "eagle-import") (part "LEDCHIP-LED0805"))
    )
    (comp (ref "LED6")
      (value "LEDCHIP-LED0805")
      (footprint "eagle-import:CHIP-LED0805")
      (libsource (lib "eagle-import") (part "LEDCHIP-LED0805"))
    )
    (comp (ref "LED7")
      (value "LEDCHIP-LED0805")
      (footprint "eagle-import:CHIP-LED0805")
      (libsource (lib "eagle-import") (part "LEDCHIP-LED0805"))
    )
    (comp (ref "R42")
      (value "680")
      (footprint "eagle-import:R0805")
      (libsource (lib "eagle-import") (part "R-EU_R0805"))
    )
    (comp (ref "R43")
      (value "1,5k")
      (footprint "eagle-import:R0805")
      (libsource (lib "eagle-import") (part "R-EU_R0805"))
    )
    (comp (ref "R44")
      (value "4.7k")
      (footprint "eagle-import:R0805")
      (libsource (lib "eagle-import") (part "R-EU_R0805"))
    )
    (comp (ref "R45")
      (value "1,5k")
      (footprint "eagle-import:R0805")
      (libsource (lib "eagle-import") (part "R-EU_R0805"))
    )
    (comp (ref "U$8")
      (value "LM2576")
      (footprint "eagle-import:TO220511")
      (libsource (lib "eagle-import") (part "LM2576"))
    )
    (comp (ref "U3")
      (value "LM2675")
      (footprint "eagle-import:SOIC127P620X175-8N")
      (fields (field (name "MPN") "LM2675M-3.3"))
      (libsource (lib "eagle-import") (part "LM2675M-3.3"))
    )
    (comp (ref "U4")
      (value "LM2675")
      (footprint "eagle-import:SOIC127P620X175-8N")
      (fields (field (name "MPN") "LM2675M-3.3"))
      (libsource (lib "eagle-import") (part "LM2675M-3.3"))
    )
    (comp (ref "X1")
      (value "AK500/2-H")
      (footprint "eagle-import:AK500_2-H")
      (libsource (lib "eagle-import") (part "AK500/2-H"))
    )
    (comp (ref "C31")
      (value "1µ")
      (footprint "eagle-import:C0603")
      (libsource (lib "eagle-import") (part "C-EUC0603"))
    )
    (comp (ref "C32")
      (value "1µ")
      (footprint "eagle-import:C0603")
      (libsource (lib "eagle-import") (part "C-EUC0603"))
    )
    (comp (ref "COIL_IN")
      (value "WIREPADSMD5-5")
      (footprint "eagle-import:5-5")
      (libsource (lib "eagle-import") (part "WIREPADSMD5-5"))
    )
    (comp (ref "COIL_OUT")
      (value "WIREPADSMD5-5")
      (footprint "eagle-import:5-5")
      (libsource (lib "eagle-import") (part "WIREPADSMD5-5"))
    )
    (comp (ref "D5")
      (value "SMD ZD 15")
      (footprint "eagle-import:TO236")
      (libsource (lib "eagle-import") (part "BZX84CSMD"))
    )
    (comp (ref "Q2")
      (value "IGW60T120")
      (footprint "eagle-import:TO247BV")
      (libsource (lib "eagle-import") (part "IRFPC40"))
    )
    (comp (ref "Q6")
      (value "IRF840")
      (footprint "eagle-import:TO220BV")
      (libsource (lib "eagle-import") (part "IRF740"))
    )
    (comp (ref "R2")
      (value "100")
      (footprint "eagle-import:HS25")
      (libsource (lib "eagle-import") (part "RHS25"))
    )
    (comp (ref "R3")
      (value "100")
      (footprint "eagle-import:HS25")
      (libsource (lib "eagle-import") (part "RHS25"))
    )
    (comp (ref "R14")
      (value "380")
      (footprint "eagle-import:R0805")
      (libsource (lib "eagle-import") (part "R-EU_R0805"))
    )
    (comp (ref "R15")
      (value "10")
      (footprint "eagle-import:R0805")
      (libsource (lib "eagle-import") (part "R-EU_R0805"))
    )
    (comp (ref "R16")
      (value "470k")
      (footprint "eagle-import:0207_15")
      (libsource (lib "eagle-import") (part "R-EU_0207/15"))
    )
    (comp (ref "R17")
      (value "380")
      (footprint "eagle-import:R0805")
      (libsource (lib "eagle-import") (part "R-EU_R0805"))
    )
    (comp (ref "R18")
      (value "10")
      (footprint "eagle-import:R0805")
      (libsource (lib "eagle-import") (part "R-EU_R0805"))
    )
    (comp (ref "R19")
      (value "3k")
      (footprint "eagle-import:R0805")
      (libsource (lib "eagle-import") (part "R-EU_R0805"))
    )
    (comp (ref "R20")
      (value "B72220S0321K101")
      (footprint "eagle-import:S20K320")
      (libsource (lib "eagle-import") (part "S20K320"))
    )
    (comp (ref "R51")
      (value "12k")
      (footprint "eagle-import:R0805")
      (libsource (lib "eagle-import") (part "R-EU_R0805"))
    )
    (comp (ref "T1")
      (value "BC849")
      (footprint "eagle-import:SOT23")
      (libsource (lib "eagle-import") (part "BC849"))
    )
    (comp (ref "T2")
      (value "BC849")
      (footprint "eagle-import:SOT23")
      (libsource (lib "eagle-import") (part "BC849"))
    )
    (comp (ref "U$5")
      (value "SI8261ABC")
      (footprint "eagle-import:SOIC-8")
      (libsource (lib "eagle-import") (part "SI8261ABC"))
    )
    (comp (ref "U$6")
      (value "SI8261ABC")
      (footprint "eagle-import:SOIC-8")
      (libsource (lib "eagle-import") (part "SI8261ABC"))
    )
    (comp (ref "U$7")
      (value "DSEI30-12A")
      (footprint "eagle-import:TO247AD")
      (libsource (lib "eagle-import") (part "DSEI30-12A"))
    )
    (comp (ref "C26")
      (value "100n")
      (footprint "eagle-import:C0603")
      (libsource (lib "eagle-import") (part "C-EUC0603"))
    )
    (comp (ref "C27")
      (value "100n")
      (footprint "eagle-import:C0603")
      (libsource (lib "eagle-import") (part "C-EUC0603"))
    )
    (comp (ref "C28")
      (value "100n")
      (footprint "eagle-import:C0603")
      (libsource (lib "eagle-import") (part "C-EUC0603"))
    )
    (comp (ref "JP1")
      (value "PINHD-1X5")
      (footprint "eagle-import:1X05")
      (libsource (lib "eagle-import") (part "PINHD-1X5"))
    )
    (comp (ref "JP2")
      (value "PINHD-1X5")
      (footprint "eagle-import:1X05")
      (libsource (lib "eagle-import") (part "PINHD-1X5"))
    )
    (comp (ref "JP3")
      (value "PINHD-1X3")
      (footprint "eagle-import:1X03")
      (libsource (lib "eagle-import") (part "PINHD-1X3"))
    )
    (comp (ref "R1")
      (value "1k")
      (footprint "eagle-import:R0805")
      (libsource (lib "eagle-import") (part "R-EU_R0805"))
    )
    (comp (ref "R32")
      (value "120")
      (footprint "eagle-import:R0805")
      (libsource (lib "eagle-import") (part "R-EU_R0805"))
    )
    (comp (ref "R47")
      (value "1k")
      (footprint "eagle-import:R0805")
      (libsource (lib "eagle-import") (part "R-EU_R0805"))
    )
    (comp (ref "RJ_1")
      (value "RJ10")
      (footprint "eagle-import:RJ10")
      (libsource (lib "eagle-import") (part "RJ10"))
    )
    (comp (ref "RJ_2")
      (value "RJ10")
      (footprint "eagle-import:RJ10")
      (libsource (lib "eagle-import") (part "RJ10"))
    )
    (comp (ref "SJ1") (value "SJ") (footprint "eagle-import:SJ") (libsource (lib "eagle-import") (part "SJ")))
    (comp (ref "T5")
      (value "NMOSSOT23")
      (footprint "eagle-import:SOT-23")
      (libsource (lib "eagle-import") (part "NMOSSOT23"))
    )
    (comp (ref "U$1")
      (value "MCP2551-I/SN")
      (footprint "eagle-import:SOIC127P600X175-8N")
      (libsource (lib "eagle-import") (part "MCP2551-I/SN"))
    )
    (comp (ref "U1")
      (value "TXB0108PWR")
      (footprint "eagle-import:SOP65P640X120-20N")
      (libsource (lib "eagle-import") (part "TXB0108PWR"))
    )
  )
  (nets
    (net (code "1") (name "+3V3") (class "Default")
      (node (ref "C2") (pin "1") (pinfunction "1_1") (pintype "passive"))
      (node (ref "C27") (pin "1") (pinfunction "1_1") (pintype "passive"))
      (node (ref "D2") (pin "A") (pinfunction "A_A") (pintype "passive"))
      (node (ref "IC3") (pin "2") (pinfunction "OUT_2") (pintype "passive"))
      (node (ref "IC3") (pin "4") (pinfunction "OUT_4") (pintype "input"))
      (node (ref "JP2") (pin "4") (pinfunction "4_4") (pintype "passive"))
      (node (ref "R42") (pin "2") (pinfunction "2_2") (pintype "passive"))
      (node (ref "U1") (pin "10") (pinfunction "OE_10") (pintype "input"))
      (node (ref "U1") (pin "2") (pinfunction "VCCA_2") (pintype "power_in"))
    )
    (net (code "2") (name "+5V") (class "Default")
      (node (ref "C1") (pin "1") (pinfunction "1_1") (pintype "passive"))
      (node (ref "C18") (pin "+") (pinfunction "+_+") (pintype "passive"))
      (node (ref "C26") (pin "1") (pinfunction "1_1") (pintype "passive"))
      (node (ref "C28") (pin "1") (pinfunction "1_1") (pintype "passive"))
      (node (ref "C34") (pin "1") (pinfunction "1_1") (pintype "passive"))
      (node (ref "C44") (pin "1") (pinfunction "1_1") (pintype "passive"))
      (node (ref "C45") (pin "1") (pinfunction "1_1") (pintype "passive"))
      (node (ref "C8") (pin "2") (pinfunction "2_2") (pintype "passive"))
      (node (ref "D2") (pin "K") (pinfunction "C_K") (pintype "passive"))
      (node (ref "IC2") (pin "16") (pinfunction "VDD_16") (pintype "power_in"))
      (node (ref "IC3") (pin "3") (pinfunction "IN_3") (pintype "input"))
      (node (ref "IC4") (pin "8") (pinfunction "V+_8") (pintype "power_in"))
      (node (ref "L5") (pin "1") (pinfunction "1_1") (pintype "passive"))
      (node (ref "OK2") (pin "8") (pinfunction "COL_8") (pintype "passive"))
      (node (ref "R17") (pin "2") (pinfunction "2_2") (pintype "passive"))
      (node (ref "R26") (pin "2") (pinfunction "2_2") (pintype "passive"))
      (node (ref "R43") (pin "2") (pinfunction "2_2") (pintype "passive"))
      (node (ref "R48") (pin "2") (pinfunction "2_2") (pintype "passive"))
      (node (ref "R_LINE") (pin "1") (pinfunction "1_1") (pintype "passive"))
      (node (ref "S1") (pin "1") (pinfunction "S_1") (pintype "passive"))
      (node (ref "S1") (pin "2") (pinfunction "S1_2") (pintype "passive"))
      (node (ref "SV1") (pin "2") (pinfunction "2_2") (pintype "passive"))
      (node (ref "U$1") (pin "3") (pinfunction "VDD_3") (pintype "power_in"))
      (node (ref "U$2") (pin "4") (pinfunction "VCC_4") (pintype "bidirectional"))
      (node (ref "U1") (pin "19") (pinfunction "VCCB_19") (pintype "power_in"))
      (node (ref "U3") (pin "4") (pinfunction "FB_4") (pintype "input"))
      (node (ref "U5") (pin "14") (pinfunction "VDD_14") (pintype "power_in"))
    )
    (net (code "3") (name "+5V{slash}1") (class "Default")
      (node (ref "C40") (pin "+") (pinfunction "+_+") (pintype "passive"))
      (node (ref "JP3") (pin "2") (pinfunction "2_2") (pintype "passive"))
      (node (ref "L1") (pin "1") (pinfunction "1_1") (pintype "passive"))
      (node (ref "R45") (pin "2") (pinfunction "2_2") (pintype "passive"))
      (node (ref "U$8") (pin "4") (pinfunction "FB_4") (pintype "bidirectional"))
    )
    (net (code "4") (name "+5V{slash}3") (class "Default")
      (node (ref "C39") (pin "1") (pinfunction "1_1") (pintype "passive"))
      (node (ref "C7") (pin "2") (pinfunction "2_2") (pintype "passive"))
      (node (ref "D14") (pin "C") (pinfunction "C_C") (pintype "passive"))
      (node (ref "OK1") (pin "6") (pinfunction "COL_6") (pintype "passive"))
      (node (ref "R27") (pin "2") (pinfunction "2_2") (pintype "passive"))
      (node (ref "R30") (pin "1") (pinfunction "1_1") (pintype "passive"))
      (node (ref "R5") (pin "2") (pinfunction "2_2") (pintype "passive"))
      (node (ref "U$2") (pin "19") (pinfunction "AVCC_19") (pintype "bidirectional"))
    )
    (net (code "5") (name "+5V{slash}4") (class "Default")
      (node (ref "C16") (pin "1") (pinfunction "1_1") (pintype "passive"))
      (node (ref "D12") (pin "C") (pinfunction "C_C") (pintype "passive"))
      (node (ref "OK1") (pin "8") (pinfunction "COL_8") (pintype "passive"))
      (node (ref "R29") (pin "1") (pinfunction "1_1") (pintype "passive"))
      (node (ref "R7") (pin "2") (pinfunction "2_2") (pintype "passive"))
    )
    (net (code "6") (name "+12V") (class "Default")
      (node (ref "C11") (pin "1") (pinfunction "1_1") (pintype "passive"))
      (node (ref "C21") (pin "+") (pinfunction "+_+") (pintype "passive"))
      (node (ref "L6") (pin "1") (pinfunction "1_1") (pintype "passive"))
      (node (ref "R44") (pin "2") (pinfunction "2_2") (pintype "passive"))
      (node (ref "U$3") (pin "12") (pinfunction "VCC_12") (pintype "bidirectional"))
      (node (ref "U4") (pin "4") (pinfunction "FB_4") (pintype "input"))
    )
    (net (code "7") (name "+24V") (class "Default")
      (node (ref "C17") (pin "+") (pinfunction "+_+") (pintype "passive"))
      (node (ref "C20") (pin "+") (pinfunction "+_+") (pintype "passive"))
      (node (ref "C3") (pin "+") (pinfunction "+_+") (pintype "passive"))
      (node (ref "C42") (pin "+") (pinfunction "+_+") (pintype "passive"))
      (node (ref "D1") (pin "K") (pinfunction "C_K") (pintype "passive"))
      (node (ref "F1") (pin "P$1") (pinfunction "1_P$1") (pintype "passive"))
      (node (ref "R30") (pin "2") (pinfunction "2_2") (pintype "passive"))
      (node (ref "U$4") (pin "1") (pinfunction "U_IN_1") (pintype "bidirectional"))
      (node (ref "U$8") (pin "1") (pinfunction "VIN_1") (pintype "bidirectional"))
      (node (ref "U3") (pin "7") (pinfunction "VIN_7") (pintype "power_in"))
      (node (ref "U4") (pin "7") (pinfunction "VIN_7") (pintype "power_in"))
    )
    (net (code "8") (name "ACTIVATE_BOOSTER") (class "Default")
      (node (ref "R24") (pin "1") (pinfunction "1_1") (pintype "passive"))
      (node (ref "R25") (pin "1") (pinfunction "1_1") (pintype "passive"))
      (node (ref "R31") (pin "2") (pinfunction "2_2") (pintype "passive"))
      (node (ref "U$2") (pin "26") (pinfunction "PB5_26") (pintype "bidirectional"))
    )
    (net (code "9") (name "ACTIVATE_SERVO") (class "Default")
      (node (ref "R47") (pin "1") (pinfunction "1_1") (pintype "passive"))
      (node (ref "U$2") (pin "13") (pinfunction "PD5_13") (pintype "bidirectional"))
    )
    (net (code "10") (name "ADC1{slash}SCK_A") (class "Default")
      (node (ref "SV1") (pin "7") (pinfunction "7_7") (pintype "passive"))
      (node (ref "U$2") (pin "12") (pinfunction "(RXD)PD4_12") (pintype "bidirectional"))
    )
    (net (code "11") (name "ADC_CAP") (class "Default")
      (node (ref "C23") (pin "1") (pinfunction "1_1") (pintype "passive"))
      (node (ref "IC4") (pin "3") (pinfunction "+IN_3") (pintype "input"))
      (node (ref "OK1") (pin "5") (pinfunction "EMIT_5") (pintype "passive"))
      (node (ref "R8") (pin "2") (pinfunction "2_2") (pintype "passive"))
      (node (ref "U$2") (pin "14") (pinfunction "PD6_14") (pintype "bidirectional"))
    )
    (net (code "12") (name "BOOSTER_24V") (class "Default")
      (node (ref "Q5") (pin "3") (pinfunction "S_3") (pintype "passive"))
      (node (ref "R12") (pin "2") (pinfunction "2_2") (pintype "passive"))
      (node (ref "R200") (pin "2") (pinfunction "2_2") (pintype "passive"))
      (node (ref "R23") (pin "1") (pinfunction "1_1") (pintype "passive"))
      (node (ref "R46") (pin "2") (pinfunction "2_2") (pintype "passive"))
      (node (ref "X2") (pin "2") (pinfunction "KL_2") (pintype "passive"))
    )
    (net (code "13") (name "BURST") (class "Default")
      (node (ref "D17") (pin "K") (pinfunction "C_K") (pintype "passive"))
      (node (ref "U$2") (pin "18") (pinfunction "PC5_18") (pintype "bidirectional"))
      (node (ref "U5") (pin "6") (pinfunction "OUTB_6") (pintype "output"))
    )
    (net (code "14") (name "CAN_H") (class "Default")
      (node (ref "RJ_1") (pin "P$3") (pinfunction "P$3_P$3") (pintype "bidirectional"))
      (node (ref "RJ_2") (pin "P$3") (pinfunction "P$3_P$3") (pintype "bidirectional"))
      (node (ref "SJ1") (pin "2") (pinfunction "2_2") (pintype "passive"))
      (node (ref "U$1") (pin "7") (pinfunction "CANH_7") (pintype "bidirectional"))
    )
    (net (code "15") (name "CAN_L") (class "Default")
      (node (ref "R32") (pin "2") (pinfunction "2_2") (pintype "passive"))
      (node (ref "RJ_1") (pin "P$2") (pinfunction "P$2_P$2") (pintype "bidirectional"))
      (node (ref "RJ_2") (pin "P$2") (pinfunction "P$2_P$2") (pintype "bidirectional"))
      (node (ref "U$1") (pin "6") (pinfunction "CANL_6") (pintype "bidirectional"))
    )
    (net (code "16") (name "CAN_RX") (class "Default")
      (node (ref "U$1") (pin "4") (pinfunction "RXD_4") (pintype "output"))
      (node (ref "U$2") (pin "7") (pinfunction "(RXCAN)PC3_7") (pintype "bidirectional"))
    )
    (net (code "17") (name "CAN_TX") (class "Default")
      (node (ref "U$1") (pin "1") (pinfunction "TXD_1") (pintype "input"))
      (node (ref "U$2") (pin "6") (pinfunction "(TXCAN)PC2_6") (pintype "bidirectional"))
    )
    (net (code "18") (name "CAP_+12V") (class "Default")
      (node (ref "C29") (pin "+") (pinfunction "+_+") (pintype "passive"))
      (node (ref "C31") (pin "1") (pinfunction "1_1") (pintype "passive"))
      (node (ref "C32") (pin "1") (pinfunction "1_1") (pintype "passive"))
      (node (ref "C43") (pin "1") (pinfunction "1_1") (pintype "passive"))
      (node (ref "IC1") (pin "8") (pinfunction "V+_8") (pintype "power_in"))
      (node (ref "R29") (pin "2") (pinfunction "2_2") (pintype "passive"))
      (node (ref "R39") (pin "2") (pinfunction "2_2") (pintype "passive"))
      (node (ref "R40") (pin "2") (pinfunction "2_2") (pintype "passive"))
      (node (ref "R41") (pin "2") (pinfunction "2_2") (pintype "passive"))
      (node (ref "R49") (pin "2") (pinfunction "2_2") (pintype "passive"))
      (node (ref "U$4") (pin "6") (pinfunction "+U_OUT_6") (pintype "bidirectional"))
      (node (ref "U$5") (pin "8") (pinfunction "VDD_8") (pintype "bidirectional"))
      (node (ref "U$6") (pin "8") (pinfunction "VDD_8") (pintype "bidirectional"))
    )
    (net (code "19") (name "CAP_-12V") (class "Default")
      (node (ref "C30") (pin "-") (pinfunction "-_-") (pintype "passive"))
      (node (ref "C43") (pin "2") (pinfunction "2_2") (pintype "passive"))
      (node (ref "IC1") (pin "4") (pinfunction "V-_4") (pintype "power_in"))
      (node (ref "LED10") (pin "C") (pinfunction "C_C") (pintype "passive"))
      (node (ref "U$4") (pin "4") (pinfunction "-U_OUT_4") (pintype "bidirectional"))
    )
    (net (code "20") (name "CAP_0V") (class "Default")
      (node (ref "C14") (pin "2") (pinfunction "2_2") (pintype "passive"))
      (node (ref "C15") (pin "2") (pinfunction "2_2") (pintype "passive"))
      (node (ref "C16") (pin "2") (pinfunction "2_2") (pintype "passive"))
      (node (ref "C25") (pin "-") (pinfunction "-_-") (pintype "passive"))
      (node (ref "C29") (pin "-") (pinfunction "-_-") (pintype "passive"))
      (node (ref "C30") (pin "+") (pinfunction "+_+") (pintype "passive"))
      (node (ref "C31") (pin "2") (pinfunction "2_2") (pintype "passive"))
      (node (ref "C32") (pin "2") (pinfunction "2_2") (pintype "passive"))
      (node (ref "C46") (pin "2") (pinfunction "2_2") (pintype "passive"))
      (node (ref "CAP_0V") (pin "P$1") (pinfunction "P_P$1") (pintype "passive"))
      (node (ref "D10") (pin "A") (pinfunction "A_A") (pintype "passive"))
      (node (ref "D11") (pin "A") (pinfunction "A_A") (pintype "passive"))
      (node (ref "D12") (pin "A") (pinfunction "A_A") (pintype "passive"))
      (node (ref "D5") (pin "A") (pinfunction "A_A") (pintype "passive"))
      (node (ref "LED9") (pin "C") (pinfunction "C_C") (pintype "passive"))
      (node (ref "OK1") (pin "4") (pinfunction "C_4") (pintype "passive"))
      (node (ref "OK2") (pin "2") (pinfunction "C_2") (pintype "passive"))
      (node (ref "Q2") (pin "S") (pinfunction "S_S") (pintype "passive"))
      (node (ref "Q6") (pin "S") (pinfunction "S_S") (pintype "passive"))
      (node (ref "R11") (pin "1") (pinfunction "1_1") (pintype "passive"))
      (node (ref "R20") (pin "1") (pinfunction "1_1") (pintype "passive"))
      (node (ref "R36") (pin "1") (pinfunction "1_1") (pintype "passive"))
      (node (ref "R37") (pin "1") (pinfunction "1_1") (pintype "passive"))
      (node (ref "R38") (pin "1") (pinfunction "1_1") (pintype "passive"))
      (node (ref "R4") (pin "1") (pinfunction "1_1") (pintype "passive"))
      (node (ref "R50") (pin "2") (pinfunction "2_2") (pintype "passive"))
      (node (ref "R6") (pin "1") (pinfunction "1_1") (pintype "passive"))
      (node (ref "T1") (pin "2") (pinfunction "E_2") (pintype "passive"))
      (node (ref "U$4") (pin "5") (pinfunction "0V_5") (pintype "bidirectional"))
      (node (ref "U$5") (pin "5") (pinfunction "GND_5") (pintype "bidirectional"))
      (node (ref "U$6") (pin "5") (pinfunction "GND_5") (pintype "bidirectional"))
      (node (ref "VR1") (pin "3") (pinfunction "A_3") (pintype "passive"))
      (node (ref "VR2") (pin "3") (pinfunction "A_3") (pintype "passive"))
      (node (ref "VR3") (pin "3") (pinfunction "A_3") (pintype "passive"))
    )
    (net (code "21") (name "CAP_330V") (class "Default")
      (node (ref "C25") (pin "+") (pinfunction "+_+") (pintype "passive"))
      (node (ref "CAP_330V") (pin "P$1") (pinfunction "P_P$1") (pintype "passive"))
      (node (ref "COIL_OUT") (pin "P$1") (pinfunction "P_P$1") (pintype "passive"))
      (node (ref "D8") (pin "K") (pinfunction "C_K") (pintype "passive"))
      (node (ref "D9") (pin "K") (pinfunction "C_K") (pintype "passive"))
      (node (ref "R101") (pin "2") (pinfunction "2_2") (pintype "passive"))
      (node (ref "R16") (pin "2") (pinfunction "2_2") (pintype "passive"))
      (node (ref "R2") (pin "1") (pinfunction "1_1") (pintype "passive"))
      (node (ref "R33") (pin "2") (pinfunction "2_2") (pintype "passive"))
      (node (ref "R34") (pin "2") (pinfunction "2_2") (pintype "passive"))
      (node (ref "R35") (pin "2") (pinfunction "2_2") (pintype "passive"))
      (node (ref "U$7") (pin "C") (pinfunction "C_C") (pintype "passive"))
    )
    (net (code "22") (name "CLKOUT_ETH") (class "Default")
      (node (ref "U1") (pin "12") (pinfunction "B8_12") (pintype "bidirectional"))
    )
    (net (code "23") (name "CLKOUT_ETH_3V") (class "Default")
      (node (ref "JP2") (pin "1") (pinfunction "1_1") (pintype "passive"))
      (node (ref "U1") (pin "9") (pinfunction "A8_9") (pintype "bidirectional"))
    )
    (net (code "24") (name "CS_ETH") (class "Default")
      (node (ref "U$2") (pin "29") (pinfunction "PD0_29") (pintype "bidirectional"))
      (node (ref "U1") (pin "13") (pinfunction "B7_13") (pintype "bidirectional"))
    )
    (net (code "25") (name "CS_ETH_3V") (class "Default")
      (node (ref "JP2") (pin "2") (pinfunction "2_2") (pintype "passive"))
      (node (ref "U1") (pin "8") (pinfunction "A7_8") (pintype "bidirectional"))
    )
    (net (code "26") (name "D2A{slash}RF_MAX") (class "Default")
      (node (ref "RF_MAX") (pin "1") (pinfunction "1_1") (pintype "passive"))
      (node (ref "U$2") (pin "25") (pinfunction "PC7_25") (pintype "bidirectional"))
    )
    (net (code "27") (name "FREI") (class "Default")
      (node (ref "U$2") (pin "16") (pinfunction "PB2_16") (pintype "bidirectional"))
    )
    (net (code "28") (name "FREI2") (class "Default")
      (node (ref "U$2") (pin "27") (pinfunction "PB6_27") (pintype "bidirectional"))
    )
    (net (code "29") (name "FREI3") (class "Default")
      (node (ref "U$2") (pin "15") (pinfunction "PD7_15") (pintype "bidirectional"))
    )
    (net (code "30") (name "GND") (class "Default")
      (node (ref "C1") (pin "2") (pinfunction "2_2") (pintype "passive"))
      (node (ref "C11") (pin "2") (pinfunction "2_2") (pintype "passive"))
      (node (ref "C12") (pin "2") (pinfunction "2_2") (pintype "passive"))
      (node (ref "C17") (pin "-") (pinfunction "-_-") (pintype "passive"))
      (node (ref "C18") (pin "-") (pinfunction "-_-") (pintype "passive"))
      (node (ref "C2") (pin "2") (pinfunction "2_2") (pintype "passive"))
      (node (ref "C20") (pin "-") (pinfunction "-_-") (pintype "passive"))
      (node (ref "C21") (pin "-") (pinfunction "-_-") (pintype "passive"))
      (node (ref "C23") (pin "2") (pinfunction "2_2") (pintype "passive"))
      (node (ref "C24") (pin "2") (pinfunction "2_2") (pintype "passive"))
      (node (ref "C26") (pin "2") (pinfunction "2_2") (pintype "passive"))
      (node (ref "C27") (pin "2") (pinfunction "2_2") (pintype "passive"))
      (node (ref "C28") (pin "2") (pinfunction "2_2") (pintype "passive"))
      (node (ref "C3") (pin "-") (pinfunction "-_-") (pintype "passive"))
      (node (ref "C33") (pin "2") (pinfunction "2_2") (pintype "passive"))
      (node (ref "C34") (pin "2") (pinfunction "2_2") (pintype "passive"))
      (node (ref "C36") (pin "2") (pinfunction "2_2") (pintype "passive"))
      (node (ref "C37") (pin "2") (pinfunction "2_2") (pintype "passive"))
      (node (ref "C38") (pin "2") (pinfunction "2_2") (pintype "passive"))
      (node (ref "C39") (pin "2") (pinfunction "2_2") (pintype "passive"))
      (node (ref "C4") (pin "1") (pinfunction "1_1") (pintype "passive"))
      (node (ref "C40") (pin "-") (pinfunction "-_-") (pintype "passive"))
      (node (ref "C42") (pin "-") (pinfunction "-_-") (pintype "passive"))
      (node (ref "C44") (pin "2") (pinfunction "2_2") (pintype "passive"))
      (node (ref "C45") (pin "2") (pinfunction "2_2") (pintype "passive"))
      (node (ref "C5") (pin "1") (pinfunction "1_1") (pintype "passive"))
      (node (ref "C6") (pin "1") (pinfunction "1_1") (pintype "passive"))
      (node (ref "C7") (pin "1") (pinfunction "1_1") (pintype "passive"))
      (node (ref "C8") (pin "1") (pinfunction "1_1") (pintype "passive"))
      (node (ref "CF") (pin "2") (pinfunction "2_2") (pintype "passive"))
      (node (ref "CSS") (pin "2") (pinfunction "2_2") (pintype "passive"))
      (node (ref "C_DELAY") (pin "2") (pinfunction "2_2") (pintype "passive"))
      (node (ref "C_ISEN_B") (pin "2") (pinfunction "2_2") (pintype "passive"))
      (node (ref "D1") (pin "A") (pinfunction "A_A") (pintype "passive"))
      (node (ref "D14") (pin "A") (pinfunction "A_A") (pintype "passive"))
      (node (ref "D15") (pin "A") (pinfunction "A_A") (pintype "passive"))
      (node (ref "D4") (pin "A") (pinfunction "A_A") (pintype "passive"))
      (node (ref "D6") (pin "A") (pinfunction "A_A") (pintype "passive"))
      (node (ref "D7") (pin "A") (pinfunction "A_A") (pintype "passive"))
      (node (ref "IC2") (pin "3") (pinfunction "R0_3") (pintype "input"))
      (node (ref "IC2") (pin "4") (pinfunction "S0_4") (pintype "input"))
      (node (ref "IC2") (pin "6") (pinfunction "S1_6") (pintype "input"))
      (node (ref "IC2") (pin "7") (pinfunction "R1_7") (pintype "input"))
      (node (ref "IC2") (pin "8") (pinfunction "VSS_8") (pintype "power_in"))
      (node (ref "IC3") (pin "1") (pinfunction "GND_1") (pintype "input"))
      (node (ref "IC4") (pin "4") (pinfunction "V-_4") (pintype "power_in"))
      (node (ref "JP2") (pin "5") (pinfunction "5_5") (pintype "passive"))
      (node (ref "LED4") (pin "C") (pinfunction "C_C") (pintype "passive"))
      (node (ref "LED5") (pin "C") (pinfunction "C_C") (pintype "passive"))
      (node (ref "LED6") (pin "C") (pinfunction "C_C") (pintype "passive"))
      (node (ref "LED7") (pin "C") (pinfunction "C_C") (pintype "passive"))
      (node (ref "R1") (pin "1") (pinfunction "1_1") (pintype "passive"))
      (node (ref "R10") (pin "1") (pinfunction "1_1") (pintype "passive"))
      (node (ref "R13") (pin "1") (pinfunction "1_1") (pintype "passive"))
      (node (ref "R21") (pin "1") (pinfunction "1_1") (pintype "passive"))
      (node (ref "R22") (pin "1") (pinfunction "1_1") (pintype "passive"))
      (node (ref "R28") (pin "1") (pinfunction "1_1") (pintype "passive"))
      (node (ref "R31") (pin "1") (pinfunction "1_1") (pintype "passive"))
      (node (ref "R51") (pin "1") (pinfunction "1_1") (pintype "passive"))
      (node (ref "R8") (pin "1") (pinfunction "1_1") (pintype "passive"))
      (node (ref "RF_MIN") (pin "1") (pinfunction "1_1") (pintype "passive"))
      (node (ref "RJ_1") (pin "P$4") (pinfunction "P$4_P$4") (pintype "bidirectional"))
      (node (ref "RJ_2") (pin "P$4") (pinfunction "P$4_P$4") (pintype "bidirectional"))
      (node (ref "R_DELAY") (pin "1") (pinfunction "1_1") (pintype "passive"))
      (node (ref "R_ISEN_B") (pin "1") (pinfunction "1_1") (pintype "passive"))
      (node (ref "SV1") (pin "10") (pinfunction "10_10") (pintype "passive"))
      (node (ref "SV1") (pin "4") (pinfunction "4_4") (pintype "passive"))
      (node (ref "SV1") (pin "6") (pinfunction "6_6") (pintype "passive"))
      (node (ref "SV1") (pin "8") (pinfunction "8_8") (pintype "passive"))
      (node (ref "T2") (pin "2") (pinfunction "E_2") (pintype "passive"))
      (node (ref "T4") (pin "2") (pinfunction "E_2") (pintype "passive"))
      (node (ref "T5") (pin "2") (pinfunction "S_2") (pintype "passive"))
      (node (ref "U$1") (pin "2") (pinfunction "VSS_2") (pintype "passive"))
      (node (ref "U$2") (pin "20") (pinfunction "AGND_20") (pintype "power_in"))
      (node (ref "U$2") (pin "5") (pinfunction "GND_5") (pintype "power_in"))
      (node (ref "U$3") (pin "10") (pinfunction "GND_10") (pintype "bidirectional"))
      (node (ref "U$3") (pin "8") (pinfunction "DIS_8") (pintype "bidirectional"))
      (node (ref "U$4") (pin "2") (pinfunction "GND_2") (pintype "bidirectional"))
      (node (ref "U$5") (pin "1") (pinfunction "NC_1") (pintype "bidirectional"))
      (node (ref "U$5") (pin "3") (pinfunction "CATHODE_3") (pintype "bidirectional"))
      (node (ref "U$5") (pin "4") (pinfunction "NC_4") (pintype "bidirectional"))
      (node (ref "U$6") (pin "1") (pinfunction "NC_1") (pintype "bidirectional"))
      (node (ref "U$6") (pin "4") (pinfunction "NC_4") (pintype "bidirectional"))
      (node (ref "U$8") (pin "3") (pinfunction "GND_3") (pintype "bidirectional"))
      (node (ref "U$8") (pin "5") (pinfunction "~{ON}/OFF_5") (pintype "bidirectional"))
      (node (ref "U1") (pin "11") (pinfunction "GND_11") (pintype "passive"))
      (node (ref "U3") (pin "6") (pinfunction "GND_6") (pintype "passive"))
      (node (ref "U4") (pin "6") (pinfunction "GND_6") (pintype "passive"))
      (node (ref "U5") (pin "11") (pinfunction "IN_1C_11") (pintype "input"))
      (node (ref "U5") (pin "13") (pinfunction "IN_3C_13") (pintype "input"))
      (node (ref "U5") (pin "5") (pinfunction "IN_3B_5") (pintype "input"))
      (node (ref "U5") (pin "7") (pinfunction "VSS_7") (pintype "passive"))
      (node (ref "U5") (pin "8") (pinfunction "IN_3A_8") (pintype "input"))
      (node (ref "X1") (pin "2") (pinfunction "KL_2") (pintype "passive"))
    )
    (net (code "31") (name "GND1") (class "Default")
      (node (ref "C10") (pin "-") (pinfunction "-_-") (pintype "passive"))
      (node (ref "C13") (pin "2") (pinfunction "2_2") (pintype "passive"))
      (node (ref "C35") (pin "2") (pinfunction "2_2") (pintype "passive"))
      (node (ref "C41") (pin "2") (pinfunction "2_2") (pintype "passive"))
      (node (ref "C9") (pin "-") (pinfunction "-_-") (pintype "passive"))
      (node (ref "LED8") (pin "C") (pinfunction "C_C") (pintype "passive"))
      (node (ref "Q4") (pin "S") (pinfunction "S_S") (pintype "passive"))
      (node (ref "R54") (pin "2") (pinfunction "2_2") (pintype "passive"))
      (node (ref "T3") (pin "2") (pinfunction "E_2") (pintype "passive"))
      (node (ref "X2") (pin "1") (pinfunction "KL_1") (pintype "passive"))
    )
    (net (code "32") (name "INT_ETH") (class "Default")
      (node (ref "U$2") (pin "30") (pinfunction "PC0_30") (pintype "bidirectional"))
      (node (ref "U1") (pin "20") (pinfunction "B1_20") (pintype "bidirectional"))
    )
    (net (code "33") (name "INT_ETH_3V") (class "Default")
      (node (ref "JP1") (pin "5") (pinfunction "5_5") (pintype "passive"))
      (node (ref "U1") (pin "1") (pinfunction "A1_1") (pintype "bidirectional"))
    )
    (net (code "34") (name "KICK") (class "Default")
      (node (ref "R19") (pin "1") (pinfunction "1_1") (pintype "passive"))
      (node (ref "U$2") (pin "23") (pinfunction "PB3_23") (pintype "bidirectional"))
    )
    (net (code "35") (name "MISO") (class "Default")
      (node (ref "U$2") (pin "8") (pinfunction "PB0_8") (pintype "bidirectional"))
      (node (ref "U1") (pin "17") (pinfunction "B3_17") (pintype "bidirectional"))
    )
    (net (code "36") (name "MISO_3V") (class "Default")
      (node (ref "JP1") (pin "3") (pinfunction "3_3") (pintype "passive"))
      (node (ref "U1") (pin "4") (pinfunction "A3_4") (pintype "bidirectional"))
    )
    (net (code "37") (name "MOSI") (class "Default")
      (node (ref "U$2") (pin "9") (pinfunction "PB1_9") (pintype "bidirectional"))
      (node (ref "U1") (pin "16") (pinfunction "B4_16") (pintype "bidirectional"))
    )
    (net (code "38") (name "MOSI_3V") (class "Default")
      (node (ref "JP1") (pin "2") (pinfunction "2_2") (pintype "passive"))
      (node (ref "U1") (pin "5") (pinfunction "A4_5") (pintype "bidirectional"))
    )
    (net (code "39") (name "NOTAUS") (class "Default")
      (node (ref "D16") (pin "K") (pinfunction "C_K") (pintype "passive"))
      (node (ref "R14") (pin "1") (pinfunction "1_1") (pintype "passive"))
      (node (ref "U$2") (pin "22") (pinfunction "PC6_22") (pintype "bidirectional"))
      (node (ref "U5") (pin "9") (pinfunction "OUTA_9") (pintype "output"))
    )
    (net (code "40") (name "Net-(COIL_IN-P)") (class "Default")
      (node (ref "COIL_IN") (pin "P$1") (pinfunction "P_P$1") (pintype "passive"))
      (node (ref "Q2") (pin "D") (pinfunction "D_D") (pintype "passive"))
      (node (ref "R20") (pin "2") (pinfunction "2_2") (pintype "passive"))
      (node (ref "U$7") (pin "A") (pinfunction "A_A") (pintype "passive"))
    )
    (net (code "41") (name "Net-(CSS-Pad1)") (class "Default")
      (node (ref "CSS") (pin "1") (pinfunction "1_1") (pintype "passive"))
      (node (ref "R_SS") (pin "1") (pinfunction "1_1") (pintype "passive"))
      (node (ref "R_SS2") (pin "1") (pinfunction "1_1") (pintype "passive"))
    )
    (net (code "42") (name "Net-(C_ISEN_A-Pad1)") (class "Default")
      (node (ref "C_ISEN_A") (pin "1") (pinfunction "1_1") (pintype "passive"))
      (node (ref "R_ISEN_A") (pin "2") (pinfunction "2_2") (pintype "passive"))
    )
    (net (code "43") (name "Net-(D3-PadA)") (class "Default")
      (node (ref "D3") (pin "A") (pinfunction "A_A") (pintype "passive"))
      (node (ref "D4") (pin "C") (pinfunction "C_C") (pintype "passive"))
      (node (ref "R_ISEN_A") (pin "1") (pinfunction "1_1") (pintype "passive"))
    )
    (net (code "44") (name "Net-(D6-C)") (class "Default")
      (node (ref "C19") (pin "2") (pinfunction "2_2") (pintype "passive"))
      (node (ref "D6") (pin "K") (pinfunction "C_K") (pintype "passive"))
      (node (ref "L5") (pin "2") (pinfunction "2_2") (pintype "passive"))
      (node (ref "U3") (pin "8") (pinfunction "VSW_8") (pintype "output"))
    )
    (net (code "45") (name "Net-(D7-C)") (class "Default")
      (node (ref "C22") (pin "2") (pinfunction "2_2") (pintype "passive"))
      (node (ref "D7") (pin "K") (pinfunction "C_K") (pintype "passive"))
      (node (ref "L6") (pin "2") (pinfunction "2_2") (pintype "passive"))
      (node (ref "U4") (pin "8") (pinfunction "VSW_8") (pintype "output"))
    )
    (net (code "46") (name "Net-(D10-C)") (class "Default")
      (node (ref "D10") (pin "K") (pinfunction "C_K") (pintype "passive"))
      (node (ref "D8") (pin "A") (pinfunction "A_A") (pintype "passive"))
      (node (ref "L7") (pin "2") (pinfunction "8_2") (pintype "passive"))
    )
    (net (code "47") (name "Net-(D11-C)") (class "Default")
      (node (ref "D11") (pin "K") (pinfunction "C_K") (pintype "passive"))
      (node (ref "D9") (pin "A") (pinfunction "A_A") (pintype "passive"))
      (node (ref "L7") (pin "4") (pinfunction "1_4") (pintype "passive"))
    )
    (net (code "48") (name "Net-(D15-C)") (class "Default")
      (node (ref "D15") (pin "K") (pinfunction "C_K") (pintype "passive"))
      (node (ref "L1") (pin "2") (pinfunction "2_2") (pintype "passive"))
      (node (ref "U$8") (pin "2") (pinfunction "VOUT_2") (pintype "bidirectional"))
    )
    (net (code "49") (name "Net-(F1-2)") (class "Default")
      (node (ref "F1") (pin "P$2") (pinfunction "2_P$2") (pintype "passive"))
      (node (ref "X1") (pin "1") (pinfunction "KL_1") (pintype "passive"))
    )
    (net (code "50") (name "Net-(IC1A-+IN)") (class "Default")
      (node (ref "C15") (pin "1") (pinfunction "1_1") (pintype "passive"))
      (node (ref "IC1") (pin "3") (pinfunction "+IN_3") (pintype "input"))
      (node (ref "IC1") (pin "5") (pinfunction "+IN_5") (pintype "input"))
      (node (ref "R101") (pin "1") (pinfunction "1_1") (pintype "passive"))
      (node (ref "R6") (pin "2") (pinfunction "2_2") (pintype "passive"))
    )
    (net (code "51") (name "Net-(IC1A--IN)") (class "Default")
      (node (ref "C14") (pin "1") (pinfunction "1_1") (pintype "passive"))
      (node (ref "IC1") (pin "2") (pinfunction "-IN_2") (pintype "input"))
      (node (ref "OK1") (pin "7") (pinfunction "EMIT_7") (pintype "passive"))
      (node (ref "R11") (pin "2") (pinfunction "2_2") (pintype "passive"))
    )
    (net (code "52") (name "Net-(IC1A-OUT)") (class "Default")
      (node (ref "IC1") (pin "1") (pinfunction "OUT_1") (pintype "output"))
      (node (ref "R105") (pin "1") (pinfunction "1_1") (pintype "passive"))
    )
    (net (code "53") (name "Net-(IC1B--IN)") (class "Default")
      (node (ref "C46") (pin "1") (pinfunction "1_1") (pintype "passive"))
      (node (ref "IC1") (pin "6") (pinfunction "-IN_6") (pintype "input"))
      (node (ref "R4") (pin "2") (pinfunction "2_2") (pintype "passive"))
      (node (ref "R7") (pin "1") (pinfunction "1_1") (pintype "passive"))
    )
    (net (code "54") (name "Net-(IC1B-OUT)") (class "Default")
      (node (ref "IC1") (pin "7") (pinfunction "OUT_7") (pintype "output"))
      (node (ref "R9") (pin "1") (pinfunction "1_1") (pintype "passive"))
    )
    (net (code "55") (name "Net-(IC2A-Q2)") (class "Default")
      (node (ref "IC2") (pin "10") (pinfunction "Q2_10") (pintype "output"))
      (node (ref "U5") (pin "1") (pinfunction "IN_1A_1") (pintype "input"))
    )
    (net (code "56") (name "Net-(IC2A-Q3)") (class "Default")
      (node (ref "IC2") (pin "1") (pinfunction "Q3_1") (pintype "output"))
      (node (ref "U5") (pin "3") (pinfunction "IN_1B_3") (pintype "input"))
    )
    (net (code "57") (name "Net-(IC4A--IN)") (class "Default")
      (node (ref "C36") (pin "1") (pinfunction "1_1") (pintype "passive"))
      (node (ref "IC4") (pin "2") (pinfunction "-IN_2") (pintype "input"))
      (node (ref "R21") (pin "2") (pinfunction "2_2") (pintype "passive"))
      (node (ref "R5") (pin "1") (pinfunction "1_1") (pintype "passive"))
      (node (ref "R52") (pin "2") (pinfunction "2_2") (pintype "passive"))
    )
    (net (code "58") (name "Net-(IC4A-OUT)") (class "Default")
      (node (ref "IC4") (pin "1") (pinfunction "OUT_1") (pintype "output"))
      (node (ref "U5") (pin "4") (pinfunction "IN_2B_4") (pintype "input"))
    )
    (net (code "59") (name "Net-(IC4B-+IN)") (class "Default")
      (node (ref "C37") (pin "1") (pinfunction "1_1") (pintype "passive"))
      (node (ref "IC4") (pin "5") (pinfunction "+IN_5") (pintype "input"))
      (node (ref "R27") (pin "1") (pinfunction "1_1") (pintype "passive"))
      (node (ref "R28") (pin "2") (pinfunction "2_2") (pintype "passive"))
    )
    (net (code "60") (name "Net-(IC4B--IN)") (class "Default")
      (node (ref "C38") (pin "1") (pinfunction "1_1") (pintype "passive"))
      (node (ref "IC4") (pin "6") (pinfunction "-IN_6") (pintype "input"))
      (node (ref "R12") (pin "1") (pinfunction "1_1") (pintype "passive"))
      (node (ref "R13") (pin "2") (pinfunction "2_2") (pintype "passive"))
    )
    (net (code "61") (name "Net-(IC4B-OUT)") (class "Default")
      (node (ref "IC4") (pin "7") (pinfunction "OUT_7") (pintype "output"))
      (node (ref "U5") (pin "12") (pinfunction "IN_2C_12") (pintype "input"))
    )
    (net (code "62") (name "Net-(L7-4)") (class "Default")
      (node (ref "L3") (pin "1") (pinfunction "1_1") (pintype "passive"))
      (node (ref "L4") (pin "1") (pinfunction "1_1") (pintype "passive"))
      (node (ref "L7") (pin "9") (pinfunction "4_9") (pintype "passive"))
    )
    (net (code "63") (name "Net-(L7-5)") (class "Default")
      (node (ref "C13") (pin "1") (pinfunction "1_1") (pintype "passive"))
      (node (ref "C41") (pin "1") (pinfunction "1_1") (pintype "passive"))
      (node (ref "C_ISEN_A") (pin "2") (pinfunction "2_2") (pintype "passive"))
      (node (ref "L3") (pin "2") (pinfunction "2_2") (pintype "passive"))
      (node (ref "L7") (pin "11") (pinfunction "5_11") (pintype "passive"))
    )
    (net (code "64") (name "Net-(LED1-PadA)") (class "Default")
      (node (ref "LED1") (pin "A") (pinfunction "A_A") (pintype "passive"))
      (node (ref "R39") (pin "1") (pinfunction "1_1") (pintype "passive"))
    )
    (net (code "65") (name "Net-(LED2-PadA)") (class "Default")
      (node (ref "LED2") (pin "A") (pinfunction "A_A") (pintype "passive"))
      (node (ref "R40") (pin "1") (pinfunction "1_1") (pintype "passive"))
    )
    (net (code "66") (name "Net-(LED3-PadA)") (class "Default")
      (node (ref "LED3") (pin "A") (pinfunction "A_A") (pintype "passive"))
      (node (ref "R41") (pin "1") (pinfunction "1_1") (pintype "passive"))
    )
    (net (code "67") (name "Net-(LED4-PadA)") (class "Default")
      (node (ref "LED4") (pin "A") (pinfunction "A_A") (pintype "passive"))
      (node (ref "R42") (pin "1") (pinfunction "1_1") (pintype "passive"))
    )
    (net (code "68") (name "Net-(LED5-PadA)") (class "Default")
      (node (ref "LED5") (pin "A") (pinfunction "A_A") (pintype "passive"))
      (node (ref "R43") (pin "1") (pinfunction "1_1") (pintype "passive"))
    )
    (net (code "69") (name "Net-(LED6-PadA)") (class "Default")
      (node (ref "LED6") (pin "A") (pinfunction "A_A") (pintype "passive"))
      (node (ref "R44") (pin "1") (pinfunction "1_1") (pintype "passive"))
    )
    (net (code "70") (name "Net-(LED7-PadA)") (class "Default")
      (node (ref "LED7") (pin "A") (pinfunction "A_A") (pintype "passive"))
      (node (ref "R45") (pin "1") (pinfunction "1_1") (pintype "passive"))
    )
    (net (code "71") (name "Net-(LED8-PadA)") (class "Default")
      (node (ref "LED8") (pin "A") (pinfunction "A_A") (pintype "passive"))
      (node (ref "R46") (pin "1") (pinfunction "1_1") (pintype "passive"))
    )
    (net (code "72") (name "Net-(LED9-PadA)") (class "Default")
      (node (ref "LED9") (pin "A") (pinfunction "A_A") (pintype "passive"))
      (node (ref "R49") (pin "1") (pinfunction "1_1") (pintype "passive"))
    )
    (net (code "73") (name "Net-(LED10-PadA)") (class "Default")
      (node (ref "LED10") (pin "A") (pinfunction "A_A") (pintype "passive"))
      (node (ref "R50") (pin "1") (pinfunction "1_1") (pintype "passive"))
    )
    (net (code "74") (name "Net-(OK1A-A)") (class "Default")
      (node (ref "OK1") (pin "1") (pinfunction "A_1") (pintype "passive"))
      (node (ref "R105") (pin "2") (pinfunction "2_2") (pintype "passive"))
    )
    (net (code "75") (name "Net-(OK1A-C)") (class "Default")
      (node (ref "OK1") (pin "2") (pinfunction "C_2") (pintype "passive"))
      (node (ref "OK1") (pin "3") (pinfunction "A_3") (pintype "passive"))
    )
    (net (code "76") (name "Net-(OK2A-A)") (class "Default")
      (node (ref "OK2") (pin "1") (pinfunction "A_1") (pintype "passive"))
      (node (ref "R9") (pin "2") (pinfunction "2_2") (pintype "passive"))
    )
    (net (code "77") (name "Net-(Q2-PadG)") (class "Default")
      (node (ref "Q2") (pin "G") (pinfunction "G_G") (pintype "passive"))
      (node (ref "R18") (pin "2") (pinfunction "2_2") (pintype "passive"))
    )
    (net (code "78") (name "Net-(Q5-D)") (class "Default")
      (node (ref "C10") (pin "+") (pinfunction "+_+") (pintype "passive"))
      (node (ref "C35") (pin "1") (pinfunction "1_1") (pintype "passive"))
      (node (ref "C9") (pin "+") (pinfunction "+_+") (pintype "passive"))
      (node (ref "Q3") (pin "D") (pinfunction "D_D") (pintype "passive"))
      (node (ref "Q5") (pin "4") (pinfunction "D_4") (pintype "passive"))
      (node (ref "R23") (pin "2") (pinfunction "2_2") (pintype "passive"))
    )
    (net (code "79") (name "Net-(Q5-G)") (class "Default")
      (node (ref "D13") (pin "C") (pinfunction "C_C") (pintype "passive"))
      (node (ref "Q5") (pin "1") (pinfunction "G_1") (pintype "passive"))
      (node (ref "R200") (pin "1") (pinfunction "1_1") (pintype "passive"))
    )
    (net (code "80") (name "Net-(Q6-PadD)") (class "Default")
      (node (ref "Q6") (pin "D") (pinfunction "D_D") (pintype "passive"))
      (node (ref "R3") (pin "2") (pinfunction "2_2") (pintype "passive"))
    )
    (net (code "81") (name "Net-(R2-Pad2)") (class "Default")
      (node (ref "R2") (pin "2") (pinfunction "2_2") (pintype "passive"))
      (node (ref "R3") (pin "1") (pinfunction "1_1") (pintype "passive"))
    )
    (net (code "82") (name "Net-(R15-Pad1)") (class "Default")
      (node (ref "R15") (pin "1") (pinfunction "1_1") (pintype "passive"))
      (node (ref "U$5") (pin "6") (pinfunction "VO_6") (pintype "bidirectional"))
      (node (ref "U$5") (pin "7") (pinfunction "VO_7") (pintype "bidirectional"))
    )
    (net (code "83") (name "Net-(R18-Pad1)") (class "Default")
      (node (ref "R18") (pin "1") (pinfunction "1_1") (pintype "passive"))
      (node (ref "U$6") (pin "6") (pinfunction "VO_6") (pintype "bidirectional"))
      (node (ref "U$6") (pin "7") (pinfunction "VO_7") (pintype "bidirectional"))
    )
    (net (code "84") (name "Net-(R32-Pad1)") (class "Default")
      (node (ref "R32") (pin "1") (pinfunction "1_1") (pintype "passive"))
      (node (ref "SJ1") (pin "1") (pinfunction "1_1") (pintype "passive"))
    )
    (net (code "85") (name "Net-(T1-B)") (class "Default")
      (node (ref "R15") (pin "2") (pinfunction "2_2") (pintype "passive"))
      (node (ref "T1") (pin "1") (pinfunction "B_1") (pintype "passive"))
    )
    (net (code "86") (name "Net-(T1-C)") (class "Default")
      (node (ref "D5") (pin "C") (pinfunction "C_C") (pintype "passive"))
      (node (ref "Q6") (pin "G") (pinfunction "G_G") (pintype "passive"))
      (node (ref "R16") (pin "1") (pinfunction "1_1") (pintype "passive"))
      (node (ref "T1") (pin "3") (pinfunction "C_3") (pintype "passive"))
    )
    (net (code "87") (name "Net-(T2-B)") (class "Default")
      (node (ref "R19") (pin "2") (pinfunction "2_2") (pintype "passive"))
      (node (ref "R51") (pin "2") (pinfunction "2_2") (pintype "passive"))
      (node (ref "T2") (pin "1") (pinfunction "B_1") (pintype "passive"))
    )
    (net (code "88") (name "Net-(T2-C)") (class "Default")
      (node (ref "T2") (pin "3") (pinfunction "C_3") (pintype "passive"))
      (node (ref "U$6") (pin "3") (pinfunction "CATHODE_3") (pintype "bidirectional"))
    )
    (net (code "89") (name "Net-(T3-B)") (class "Default")
      (node (ref "R24") (pin "2") (pinfunction "2_2") (pintype "passive"))
      (node (ref "T3") (pin "1") (pinfunction "B_1") (pintype "passive"))
    )
    (net (code "90") (name "Net-(T3-C)") (class "Default")
      (node (ref "D13") (pin "A") (pinfunction "A_A") (pintype "passive"))
      (node (ref "T3") (pin "3") (pinfunction "C_3") (pintype "passive"))
    )
    (net (code "91") (name "Net-(T4-B)") (class "Default")
      (node (ref "R25") (pin "2") (pinfunction "2_2") (pintype "passive"))
      (node (ref "T4") (pin "1") (pinfunction "B_1") (pintype "passive"))
    )
    (net (code "92") (name "Net-(T4-C)") (class "Default")
      (node (ref "R26") (pin "1") (pinfunction "1_1") (pintype "passive"))
      (node (ref "T4") (pin "3") (pinfunction "C_3") (pintype "passive"))
      (node (ref "U5") (pin "2") (pinfunction "IN_2A_2") (pintype "input"))
    )
    (net (code "93") (name "Net-(T5-D)") (class "Default")
      (node (ref "JP3") (pin "3") (pinfunction "3_3") (pintype "passive"))
      (node (ref "T5") (pin "1") (pinfunction "D_1") (pintype "passive"))
    )
    (net (code "94") (name "Net-(T5-G)") (class "Default")
      (node (ref "R47") (pin "2") (pinfunction "2_2") (pintype "passive"))
      (node (ref "T5") (pin "3") (pinfunction "G_3") (pintype "passive"))
    )
    (net (code "95") (name "Net-(U$1-RS)") (class "Default")
      (node (ref "R1") (pin "2") (pinfunction "2_2") (pintype "passive"))
      (node (ref "U$1") (pin "8") (pinfunction "RS_8") (pintype "input"))
    )
    (net (code "96") (name "Net-(U$2-AREF)") (class "Default")
      (node (ref "C6") (pin "2") (pinfunction "2_2") (pintype "passive"))
      (node (ref "U$2") (pin "21") (pinfunction "AREF_21") (pintype "bidirectional"))
    )
    (net (code "97") (name "Net-(U$2-PE1(XTAL1))") (class "Default")
      (node (ref "C5") (pin "2") (pinfunction "2_2") (pintype "passive"))
      (node (ref "Q1") (pin "1") (pinfunction "1_1") (pintype "passive"))
      (node (ref "U$2") (pin "10") (pinfunction "PE1(XTAL1)_10") (pintype "bidirectional"))
    )
    (net (code "98") (name "Net-(U$2-PE2(XTAL2))") (class "Default")
      (node (ref "C4") (pin "2") (pinfunction "2_2") (pintype "passive"))
      (node (ref "Q1") (pin "2") (pinfunction "2_2") (pintype "passive"))
      (node (ref "U$2") (pin "11") (pinfunction "PE2(XTAL2)_11") (pintype "bidirectional"))
    )
    (net (code "99") (name "Net-(U$3-CF)") (class "Default")
      (node (ref "CF") (pin "1") (pinfunction "1_1") (pintype "passive"))
      (node (ref "U$3") (pin "3") (pinfunction "CF_3") (pintype "bidirectional"))
    )
    (net (code "100") (name "Net-(U$3-CSS)") (class "Default")
      (node (ref "R_SS2") (pin "2") (pinfunction "2_2") (pintype "passive"))
      (node (ref "U$3") (pin "1") (pinfunction "CSS_1") (pintype "bidirectional"))
    )
    (net (code "101") (name "Net-(U$3-DELAY)") (class "Default")
      (node (ref "C_DELAY") (pin "1") (pinfunction "1_1") (pintype "passive"))
      (node (ref "R_DELAY") (pin "2") (pinfunction "2_2") (pintype "passive"))
      (node (ref "U$3") (pin "2") (pinfunction "DELAY_2") (pintype "bidirectional"))
    )
    (net (code "102") (name "Net-(U$3-HVG)") (class "Default")
      (node (ref "Q3") (pin "G") (pinfunction "G_G") (pintype "passive"))
      (node (ref "R53") (pin "1") (pinfunction "1_1") (pintype "passive"))
      (node (ref "U$3") (pin "15") (pinfunction "HVG_15") (pintype "bidirectional"))
    )
    (net (code "103") (name "Net-(U$3-ISEN)") (class "Default")
      (node (ref "C_ISEN_B") (pin "1") (pinfunction "1_1") (pintype "passive"))
      (node (ref "D3") (pin "C") (pinfunction "C_C") (pintype "passive"))
      (node (ref "R_ISEN_B") (pin "2") (pinfunction "2_2") (pintype "passive"))
      (node (ref "U$3") (pin "6") (pinfunction "ISEN_6") (pintype "bidirectional"))
    )
    (net (code "104") (name "Net-(U$3-LINE)") (class "Default")
      (node (ref "R_LINE") (pin "2") (pinfunction "2_2") (pintype "passive"))
      (node (ref "U$3") (pin "7") (pinfunction "LINE_7") (pintype "bidirectional"))
    )
    (net (code "105") (name "Net-(U$3-LVG)") (class "Default")
      (node (ref "Q4") (pin "G") (pinfunction "G_G") (pintype "passive"))
      (node (ref "R54") (pin "1") (pinfunction "1_1") (pintype "passive"))
      (node (ref "U$3") (pin "11") (pinfunction "LVG_11") (pintype "bidirectional"))
    )
    (net (code "106") (name "Net-(U$3-OUT)") (class "Default")
      (node (ref "C_BOOT") (pin "2") (pinfunction "2_2") (pintype "passive"))
      (node (ref "L4") (pin "2") (pinfunction "2_2") (pintype "passive"))
      (node (ref "Q3") (pin "S") (pinfunction "S_S") (pintype "passive"))
      (node (ref "Q4") (pin "D") (pinfunction "D_D") (pintype "passive"))
      (node (ref "R53") (pin "2") (pinfunction "2_2") (pintype "passive"))
      (node (ref "U$3") (pin "14") (pinfunction "OUT_14") (pintype "bidirectional"))
    )
    (net (code "107") (name "Net-(U$3-RFMIN)") (class "Default")
      (node (ref "RF_MAX") (pin "2") (pinfunction "2_2") (pintype "passive"))
      (node (ref "RF_MIN") (pin "2") (pinfunction "2_2") (pintype "passive"))
      (node (ref "R_SS") (pin "2") (pinfunction "2_2") (pintype "passive"))
      (node (ref "U$3") (pin "4") (pinfunction "RFMIN_4") (pintype "bidirectional"))
    )
    (net (code "108") (name "Net-(U$3-VBOOT)") (class "Default")
      (node (ref "C_BOOT") (pin "1") (pinfunction "1_1") (pintype "passive"))
      (node (ref "U$3") (pin "16") (pinfunction "VBOOT_16") (pintype "bidirectional"))
    )
    (net (code "109") (name "Net-(U$5-ANODE)") (class "Default")
      (node (ref "R14") (pin "2") (pinfunction "2_2") (pintype "passive"))
      (node (ref "U$5") (pin "2") (pinfunction "ANODE_2") (pintype "bidirectional"))
    )
    (net (code "110") (name "Net-(U$6-ANODE)") (class "Default")
      (node (ref "R17") (pin "1") (pinfunction "1_1") (pintype "passive"))
      (node (ref "U$6") (pin "2") (pinfunction "ANODE_2") (pintype "bidirectional"))
    )
    (net (code "111") (name "Net-(U3-CB)") (class "Default")
      (node (ref "C19") (pin "1") (pinfunction "1_1") (pintype "passive"))
      (node (ref "U3") (pin "1") (pinfunction "CB_1") (pintype "input"))
    )
    (net (code "112") (name "Net-(U4-CB)") (class "Default")
      (node (ref "C22") (pin "1") (pinfunction "1_1") (pintype "passive"))
      (node (ref "U4") (pin "1") (pinfunction "CB_1") (pintype "input"))
    )
    (net (code "113") (name "Net-(VR1-C)") (class "Default")
      (node (ref "LED1") (pin "C") (pinfunction "C_C") (pintype "passive"))
      (node (ref "VR1") (pin "1") (pinfunction "C_1") (pintype "passive"))
    )
    (net (code "114") (name "Net-(VR1-R)") (class "Default")
      (node (ref "R33") (pin "1") (pinfunction "1_1") (pintype "passive"))
      (node (ref "R36") (pin "2") (pinfunction "2_2") (pintype "passive"))
      (node (ref "VR1") (pin "2") (pinfunction "R_2") (pintype "passive"))
    )
    (net (code "115") (name "Net-(VR2-C)") (class "Default")
      (node (ref "LED2") (pin "C") (pinfunction "C_C") (pintype "passive"))
      (node (ref "VR2") (pin "1") (pinfunction "C_1") (pintype "passive"))
    )
    (net (code "116") (name "Net-(VR2-R)") (class "Default")
      (node (ref "R34") (pin "1") (pinfunction "1_1") (pintype "passive"))
      (node (ref "R37") (pin "2") (pinfunction "2_2") (pintype "passive"))
      (node (ref "VR2") (pin "2") (pinfunction "R_2") (pintype "passive"))
    )
    (net (code "117") (name "Net-(VR3-C)") (class "Default")
      (node (ref "LED3") (pin "C") (pinfunction "C_C") (pintype "passive"))
      (node (ref "VR3") (pin "1") (pinfunction "C_1") (pintype "passive"))
    )
    (net (code "118") (name "Net-(VR3-R)") (class "Default")
      (node (ref "R35") (pin "1") (pinfunction "1_1") (pintype "passive"))
      (node (ref "R38") (pin "2") (pinfunction "2_2") (pintype "passive"))
      (node (ref "VR3") (pin "2") (pinfunction "R_2") (pintype "passive"))
    )
    (net (code "119") (name "OC0A{slash}MOSI_A") (class "Default")
      (node (ref "SV1") (pin "1") (pinfunction "1_1") (pintype "passive"))
    )
    (net (code "120") (name "OC0A{slash}MOSI_A{slash}KICK_VOLTAGE") (class "Default")
      (node (ref "R52") (pin "1") (pinfunction "1_1") (pintype "passive"))
      (node (ref "U$2") (pin "2") (pinfunction "(MOSI_A/TXD)PD3_2") (pintype "bidirectional"))
    )
    (net (code "121") (name "OC1A{slash}MISO_A") (class "Default")
      (node (ref "SV1") (pin "9") (pinfunction "9_9") (pintype "passive"))
      (node (ref "U$2") (pin "1") (pinfunction "(MISO_A)PD2_1") (pintype "bidirectional"))
    )
    (net (code "122") (name "RESET_NOTAUS") (class "Default")
      (node (ref "IC2") (pin "11") (pinfunction "R2_11") (pintype "input"))
      (node (ref "IC2") (pin "15") (pinfunction "R3_15") (pintype "input"))
      (node (ref "U$2") (pin "24") (pinfunction "PB4_24") (pintype "bidirectional"))
    )
    (net (code "123") (name "RST") (class "Default")
      (node (ref "SV1") (pin "5") (pinfunction "5_5") (pintype "passive"))
      (node (ref "U$2") (pin "31") (pinfunction "PE0(RESET)_31") (pintype "input"))
    )
    (net (code "124") (name "RST_ETH") (class "Default")
      (node (ref "U$2") (pin "32") (pinfunction "PD1_32") (pintype "bidirectional"))
      (node (ref "U1") (pin "14") (pinfunction "B6_14") (pintype "bidirectional"))
    )
    (net (code "125") (name "RST_ETH_3V") (class "Default")
      (node (ref "JP2") (pin "3") (pinfunction "3_3") (pintype "passive"))
      (node (ref "U1") (pin "7") (pinfunction "A6_7") (pintype "bidirectional"))
    )
    (net (code "126") (name "SCK") (class "Default")
      (node (ref "U$2") (pin "28") (pinfunction "(SCK)PB7_28") (pintype "bidirectional"))
      (node (ref "U1") (pin "15") (pinfunction "B5_15") (pintype "bidirectional"))
    )
    (net (code "127") (name "SCK_3V") (class "Default")
      (node (ref "JP1") (pin "1") (pinfunction "1_1") (pintype "passive"))
      (node (ref "U1") (pin "6") (pinfunction "A5_6") (pintype "bidirectional"))
    )
    (net (code "128") (name "SERVO_PWM") (class "Default")
      (node (ref "JP3") (pin "1") (pinfunction "1_1") (pintype "passive"))
      (node (ref "U$2") (pin "3") (pinfunction "PC1_3") (pintype "bidirectional"))
    )
    (net (code "129") (name "STBY") (class "Default")
      (node (ref "C12") (pin "1") (pinfunction "1_1") (pintype "passive"))
      (node (ref "D16") (pin "A") (pinfunction "A_A") (pintype "passive"))
      (node (ref "D17") (pin "A") (pinfunction "A_A") (pintype "passive"))
      (node (ref "R48") (pin "1") (pinfunction "1_1") (pintype "passive"))
      (node (ref "U$2") (pin "17") (pinfunction "PC4_17") (pintype "bidirectional"))
      (node (ref "U$3") (pin "5") (pinfunction "STBY_5") (pintype "bidirectional"))
    )
    (net (code "130") (name "TASTER") (class "Default")
      (node (ref "C33") (pin "1") (pinfunction "1_1") (pintype "passive"))
      (node (ref "IC2") (pin "14") (pinfunction "S3_14") (pintype "input"))
      (node (ref "R22") (pin "2") (pinfunction "2_2") (pintype "passive"))
      (node (ref "S1") (pin "3") (pinfunction "P_3") (pintype "passive"))
      (node (ref "S1") (pin "4") (pinfunction "P1_4") (pintype "passive"))
    )
    (net (code "131") (name "WOL_ETH") (class "Default")
      (node (ref "U1") (pin "18") (pinfunction "B2_18") (pintype "bidirectional"))
    )
    (net (code "132") (name "WOL_ETH_3V") (class "Default")
      (node (ref "JP1") (pin "4") (pinfunction "4_4") (pintype "passive"))
      (node (ref "U1") (pin "3") (pinfunction "A2_3") (pintype "bidirectional"))
    )
    (net (code "133") (name "unconnected-(H1-MOUNT-PadB3,0)") (class "Default")
      (node (ref "H1") (pin "B3,0") (pinfunction "MOUNT_B3,0") (pintype "passive"))
    )
    (net (code "134") (name "unconnected-(H2-MOUNT-PadB3,0)") (class "Default")
      (node (ref "H2") (pin "B3,0") (pinfunction "MOUNT_B3,0") (pintype "passive"))
    )
    (net (code "135") (name "unconnected-(H3-MOUNT-PadB3,0)") (class "Default")
      (node (ref "H3") (pin "B3,0") (pinfunction "MOUNT_B3,0") (pintype "passive"))
    )
    (net (code "136") (name "unconnected-(H4-MOUNT-PadB3,0)") (class "Default")
      (node (ref "H4") (pin "B3,0") (pinfunction "MOUNT_B3,0") (pintype "passive"))
    )
    (net (code "137") (name "unconnected-(IC2A-EN-Pad5)") (class "Default")
      (node (ref "IC2") (pin "5") (pinfunction "EN_5") (pintype "input"))
    )
    (net (code "138") (name "unconnected-(IC2A-Q0-Pad2)") (class "Default")
      (node (ref "IC2") (pin "2") (pinfunction "Q0_2") (pintype "output"))
    )
    (net (code "139") (name "unconnected-(IC2A-Q1-Pad9)") (class "Default")
      (node (ref "IC2") (pin "9") (pinfunction "Q1_9") (pintype "output"))
    )
    (net (code "140") (name "unconnected-(L7-2-Pad8)") (class "Default")
      (node (ref "L7") (pin "8") (pinfunction "2_8") (pintype "passive"))
    )
    (net (code "141") (name "unconnected-(L7-3-Pad10)") (class "Default")
      (node (ref "L7") (pin "10") (pinfunction "3_10") (pintype "passive"))
    )
    (net (code "142") (name "unconnected-(L7-7-Pad5)") (class "Default")
      (node (ref "L7") (pin "5") (pinfunction "7_5") (pintype "passive"))
    )
    (net (code "143") (name "unconnected-(L7-Pad6)") (class "Default")
      (node (ref "L7") (pin "6") (pinfunction "6_6") (pintype "passive"))
    )
    (net (code "144") (name "unconnected-(OK2B-A-Pad3)") (class "Default")
      (node (ref "OK2") (pin "3") (pinfunction "A_3") (pintype "passive"))
    )
    (net (code "145") (name "unconnected-(OK2B-C-Pad4)") (class "Default")
      (node (ref "OK2") (pin "4") (pinfunction "C_4") (pintype "passive"))
    )
    (net (code "146") (name "unconnected-(OK2B-COL-Pad6)") (class "Default")
      (node (ref "OK2") (pin "6") (pinfunction "COL_6") (pintype "passive"))
    )
    (net (code "147") (name "unconnected-(OK2B-EMIT-Pad5)") (class "Default")
      (node (ref "OK2") (pin "5") (pinfunction "EMIT_5") (pintype "passive"))
    )
    (net (code "148") (name "unconnected-(RJ_1-PadP$1)") (class "Default")
      (node (ref "RJ_1") (pin "P$1") (pinfunction "P$1_P$1") (pintype "bidirectional"))
    )
    (net (code "149") (name "unconnected-(RJ_2-PadP$1)") (class "Default")
      (node (ref "RJ_2") (pin "P$1") (pinfunction "P$1_P$1") (pintype "bidirectional"))
    )
    (net (code "150") (name "unconnected-(SV1-Pad3)") (class "Default")
      (node (ref "SV1") (pin "3") (pinfunction "3_3") (pintype "passive"))
    )
    (net (code "151") (name "unconnected-(U$1-VREF-Pad5)") (class "Default")
      (node (ref "U$1") (pin "5") (pinfunction "VREF_5") (pintype "output"))
    )
    (net (code "152") (name "unconnected-(U$3-NC-Pad13)") (class "Default")
      (node (ref "U$3") (pin "13") (pinfunction "NC_13") (pintype "bidirectional"))
    )
    (net (code "153") (name "unconnected-(U$3-PFC_STOP-Pad9)") (class "Default")
      (node (ref "U$3") (pin "9") (pinfunction "PFC_STOP_9") (pintype "bidirectional"))
    )
    (net (code "154") (name "unconnected-(U3-NC-Pad3)") (class "Default")
      (node (ref "U3") (pin "3") (pinfunction "NC_3") (pintype "no_connect"))
    )
    (net (code "155") (name "unconnected-(U3-NC_2-Pad2)") (class "Default")
      (node (ref "U3") (pin "2") (pinfunction "NC_2_2") (pintype "no_connect"))
    )
    (net (code "156") (name "unconnected-(U3-ON{slash}~{OFF}-Pad5)") (class "Default")
      (node (ref "U3") (pin "5") (pinfunction "ON/~{OFF}_5") (pintype "input"))
    )
    (net (code "157") (name "unconnected-(U4-NC-Pad3)") (class "Default")
      (node (ref "U4") (pin "3") (pinfunction "NC_3") (pintype "no_connect"))
    )
    (net (code "158") (name "unconnected-(U4-NC_2-Pad2)") (class "Default")
      (node (ref "U4") (pin "2") (pinfunction "NC_2_2") (pintype "no_connect"))
    )
    (net (code "159") (name "unconnected-(U4-ON{slash}~{OFF}-Pad5)") (class "Default")
      (node (ref "U4") (pin "5") (pinfunction "ON/~{OFF}_5") (pintype "input"))
    )
    (net (code "160") (name "unconnected-(U5-OUTC-Pad10)") (class "Default")
      (node (ref "U5") (pin "10") (pinfunction "OUTC_10") (pintype "output"))
    )
    (net (code "161") (name "ÜBERSPANNUNG") (class "Default")
      (node (ref "C24") (pin "1") (pinfunction "1_1") (pintype "passive"))
      (node (ref "IC2") (pin "12") (pinfunction "S2_12") (pintype "input"))
      (node (ref "OK2") (pin "7") (pinfunction "EMIT_7") (pintype "passive"))
      (node (ref "R10") (pin "2") (pinfunction "2_2") (pintype "passive"))
    )
  )
)
